# ETH_SWITCH.net
KiCad netlist of a schematic drawn in Altium Designer
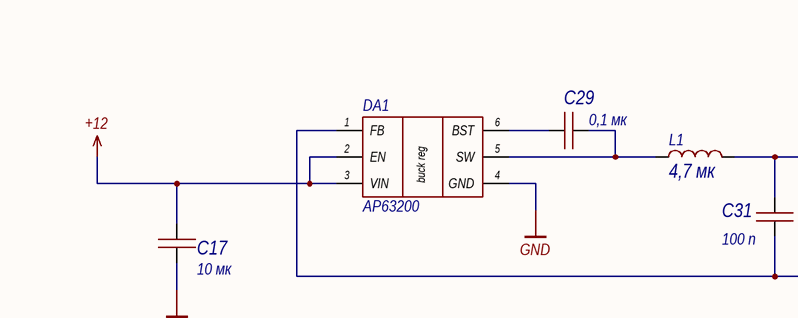
[diagram p0: ETH_SWITCH.SchDoc, top left]
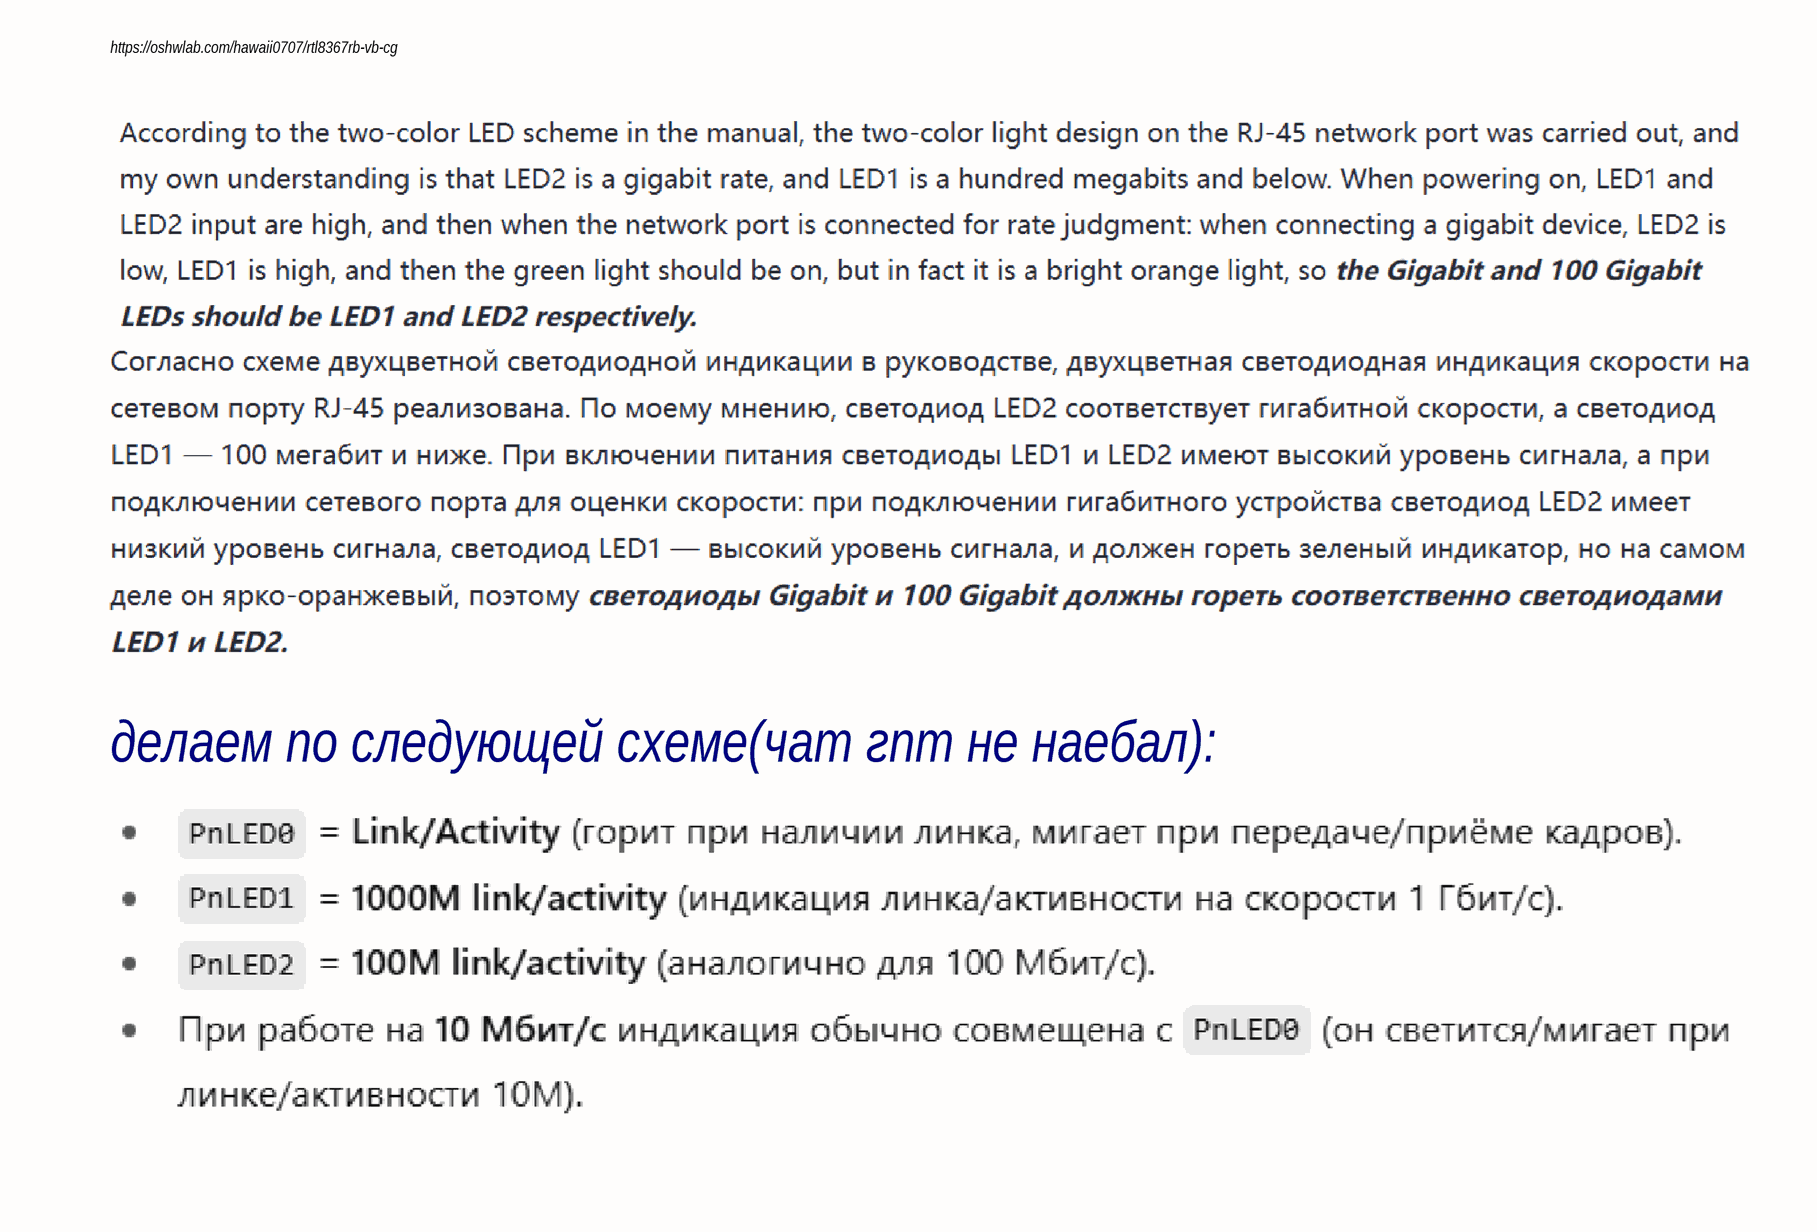
[diagram p1: ETH_SWITCH.SchDoc, top right]
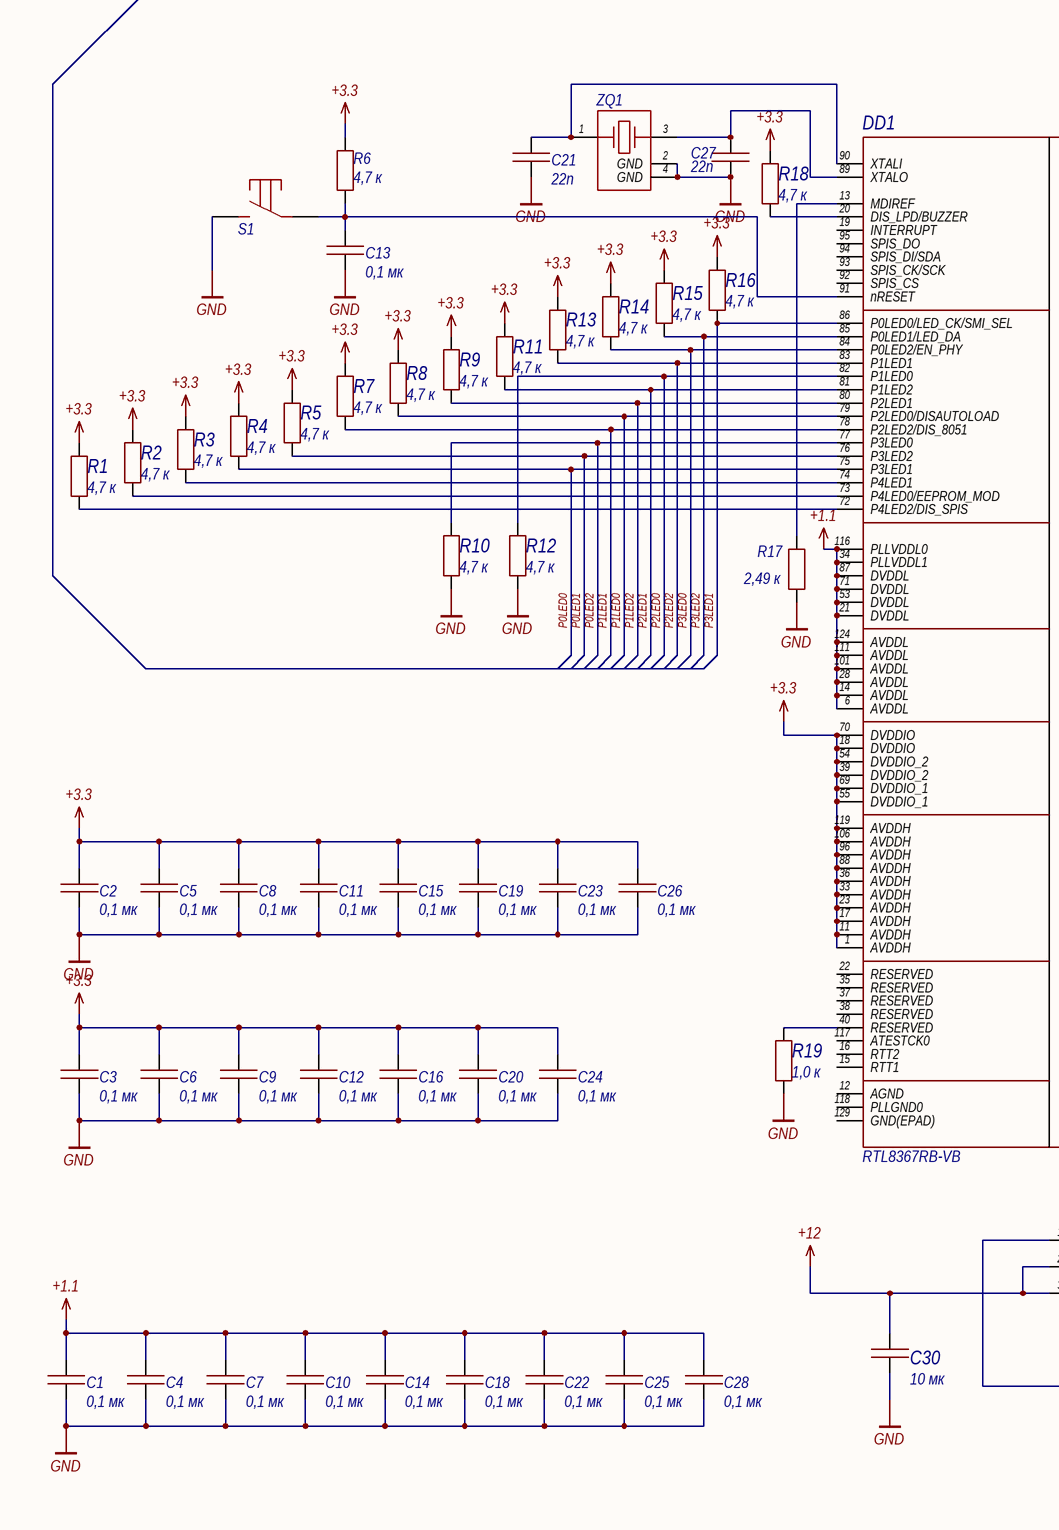
[diagram p2: ETH_SWITCH.SchDoc, bottom left]
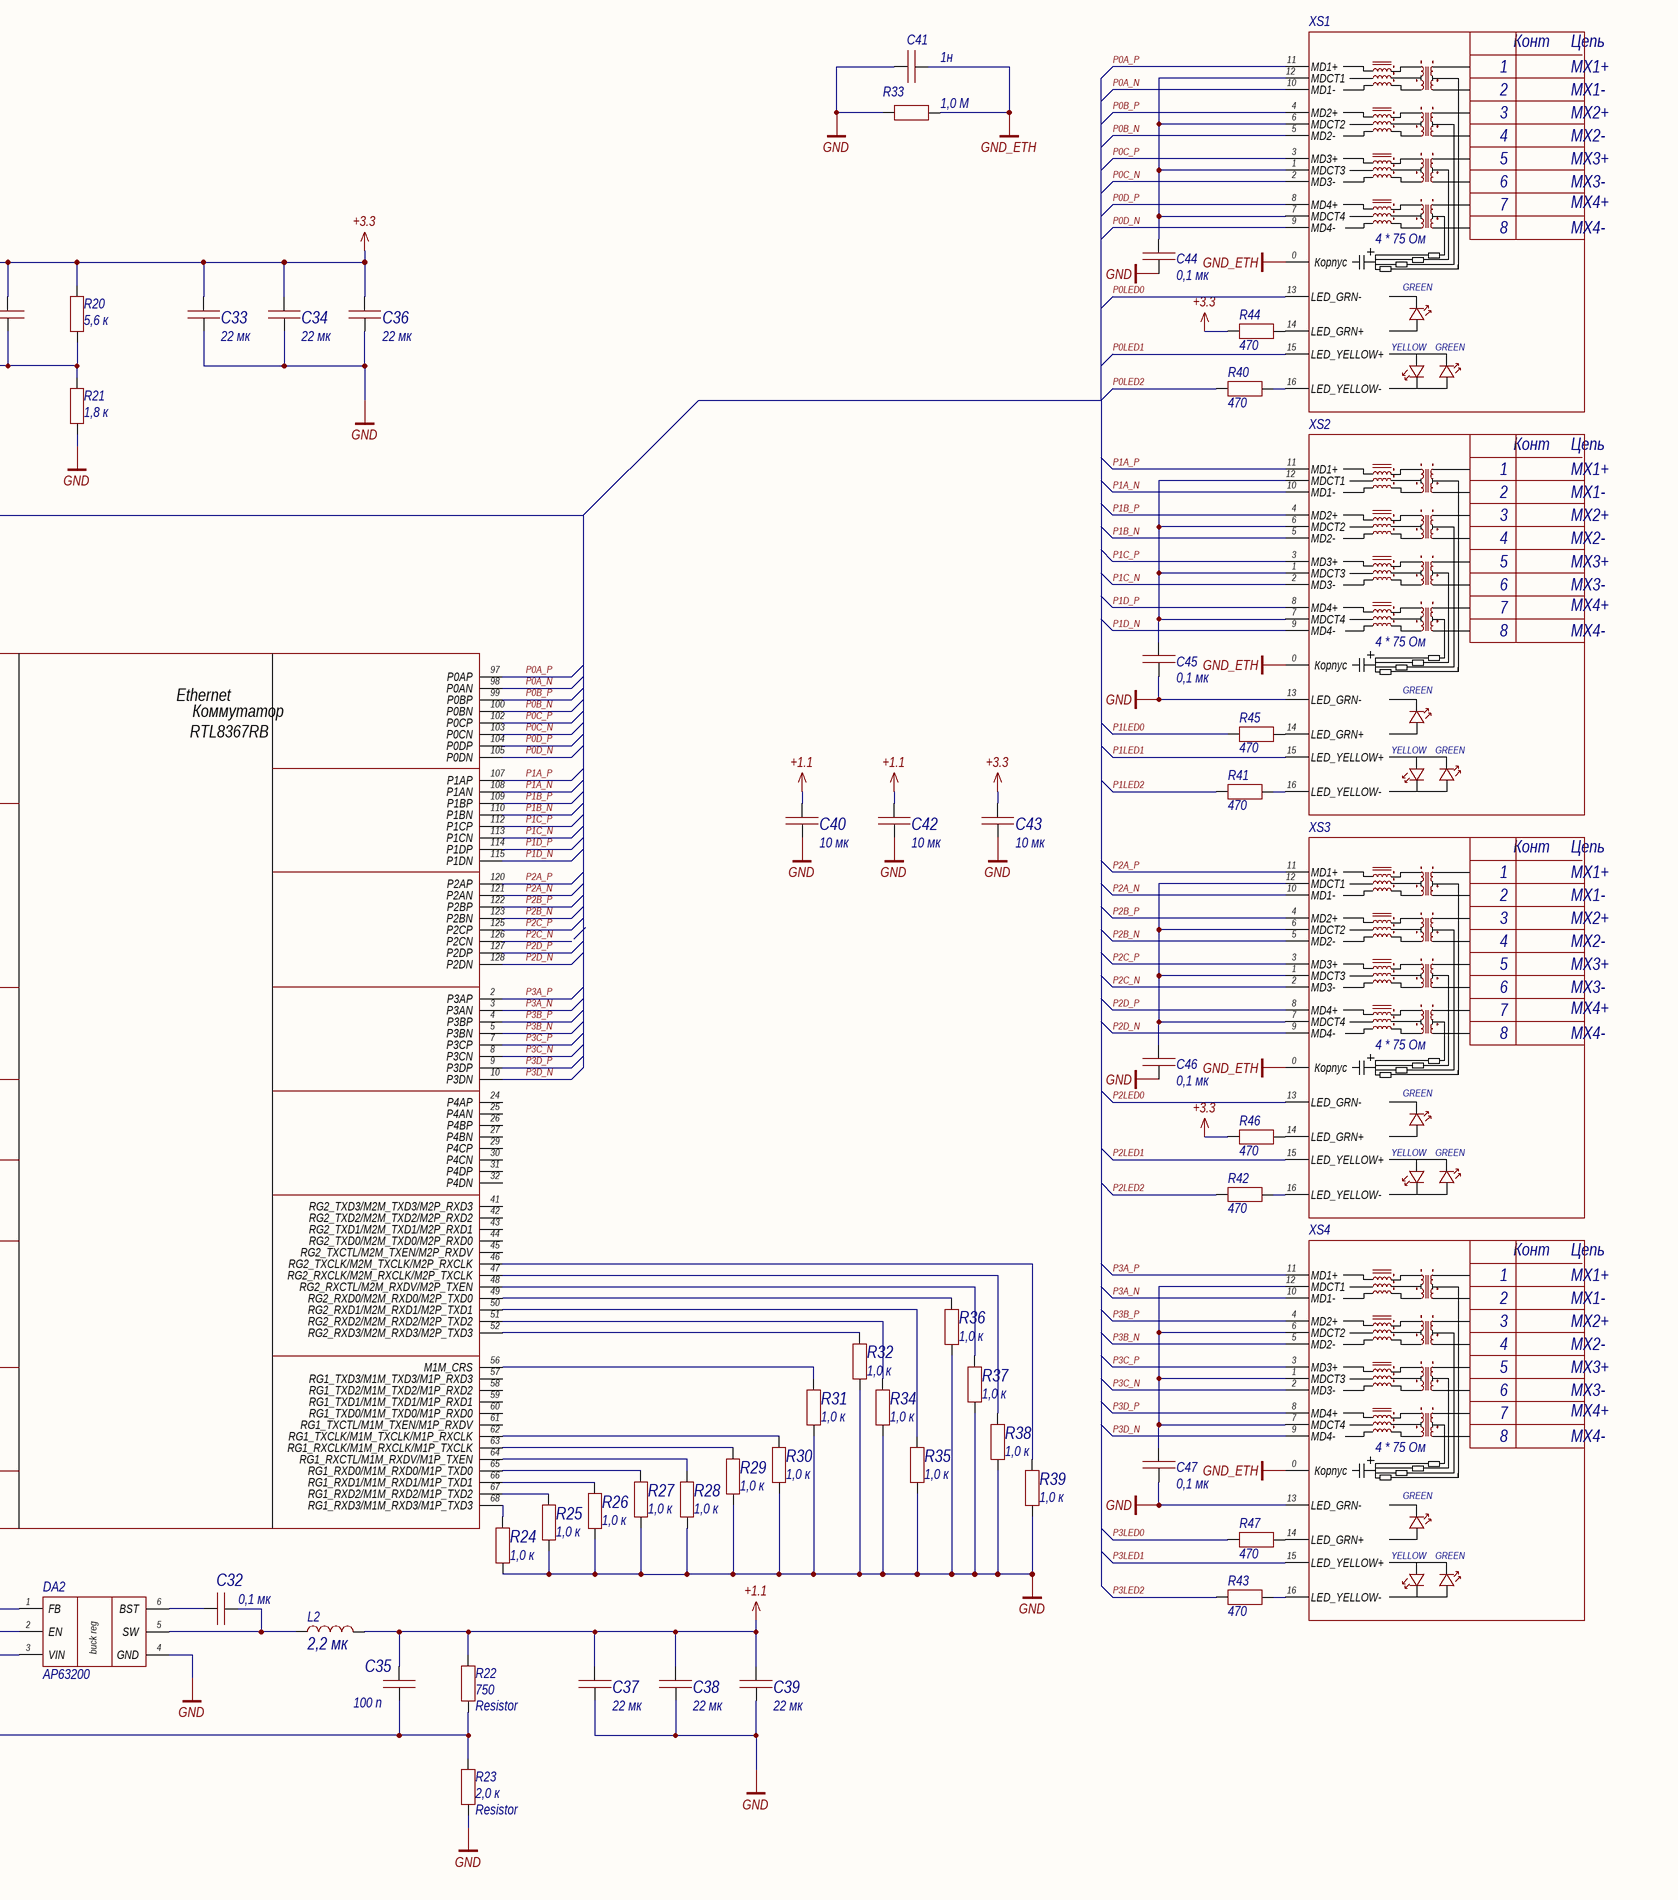
[diagram p3: ETH_SWITCH.SchDoc, bottom right]

(export (version "E")
  (design (tool "Eeschema 10.0.6"))
  (components
    (comp (ref "C1")
      (value "0,1 мк")
      (footprint "0402C")
      (description "Конденсатор 0402C ёмкостью 0,1 мк 10%, 16 В, X7R")
      (fields
        (field (name "PART NUMBER") "Capacitor_0,1u_10_16V_X7R_0603C")
        (field (name "TOLERANCE") "10%")
        (field (name "АВТОР") "rreali")
      )
      (libsource (lib "Hydrolib") (part "Capacitor"))
    )
    (comp (ref "C2")
      (value "0,1 мк")
      (footprint "0402C")
      (description "Конденсатор 0402C ёмкостью 0,1 мк 10%, 16 В, X7R")
      (fields
        (field (name "PART NUMBER") "Capacitor_0,1u_10_16V_X7R_0603C")
        (field (name "TOLERANCE") "10%")
        (field (name "АВТОР") "rreali")
      )
      (libsource (lib "Hydrolib") (part "Capacitor"))
    )
    (comp (ref "C3")
      (value "0,1 мк")
      (footprint "0402C")
      (description "Конденсатор 0402C ёмкостью 0,1 мк 10%, 16 В, X7R")
      (fields
        (field (name "PART NUMBER") "Capacitor_0,1u_10_16V_X7R_0603C")
        (field (name "TOLERANCE") "10%")
        (field (name "АВТОР") "rreali")
      )
      (libsource (lib "Hydrolib") (part "Capacitor"))
    )
    (comp (ref "C4")
      (value "0,1 мк")
      (footprint "0402C")
      (description "Конденсатор 0402C ёмкостью 0,1 мк 10%, 16 В, X7R")
      (fields
        (field (name "PART NUMBER") "Capacitor_0,1u_10_16V_X7R_0603C")
        (field (name "TOLERANCE") "10%")
        (field (name "АВТОР") "rreali")
      )
      (libsource (lib "Hydrolib") (part "Capacitor"))
    )
    (comp (ref "C5")
      (value "0,1 мк")
      (footprint "0402C")
      (description "Конденсатор 0402C ёмкостью 0,1 мк 10%, 16 В, X7R")
      (fields
        (field (name "PART NUMBER") "Capacitor_0,1u_10_16V_X7R_0603C")
        (field (name "TOLERANCE") "10%")
        (field (name "АВТОР") "rreali")
      )
      (libsource (lib "Hydrolib") (part "Capacitor"))
    )
    (comp (ref "C6")
      (value "0,1 мк")
      (footprint "0402C")
      (description "Конденсатор 0402C ёмкостью 0,1 мк 10%, 16 В, X7R")
      (fields
        (field (name "PART NUMBER") "Capacitor_0,1u_10_16V_X7R_0603C")
        (field (name "TOLERANCE") "10%")
        (field (name "АВТОР") "rreali")
      )
      (libsource (lib "Hydrolib") (part "Capacitor"))
    )
    (comp (ref "C7")
      (value "0,1 мк")
      (footprint "0402C")
      (description "Конденсатор 0402C ёмкостью 0,1 мк 10%, 16 В, X7R")
      (fields
        (field (name "PART NUMBER") "Capacitor_0,1u_10_16V_X7R_0603C")
        (field (name "TOLERANCE") "10%")
        (field (name "АВТОР") "rreali")
      )
      (libsource (lib "Hydrolib") (part "Capacitor"))
    )
    (comp (ref "C8")
      (value "0,1 мк")
      (footprint "0402C")
      (description "Конденсатор 0402C ёмкостью 0,1 мк 10%, 16 В, X7R")
      (fields
        (field (name "PART NUMBER") "Capacitor_0,1u_10_16V_X7R_0603C")
        (field (name "TOLERANCE") "10%")
        (field (name "АВТОР") "rreali")
      )
      (libsource (lib "Hydrolib") (part "Capacitor"))
    )
    (comp (ref "C9")
      (value "0,1 мк")
      (footprint "0402C")
      (description "Конденсатор 0402C ёмкостью 0,1 мк 10%, 16 В, X7R")
      (fields
        (field (name "PART NUMBER") "Capacitor_0,1u_10_16V_X7R_0603C")
        (field (name "TOLERANCE") "10%")
        (field (name "АВТОР") "rreali")
      )
      (libsource (lib "Hydrolib") (part "Capacitor"))
    )
    (comp (ref "C10")
      (value "0,1 мк")
      (footprint "0402C")
      (description "Конденсатор 0402C ёмкостью 0,1 мк 10%, 16 В, X7R")
      (fields
        (field (name "PART NUMBER") "Capacitor_0,1u_10_16V_X7R_0603C")
        (field (name "TOLERANCE") "10%")
        (field (name "АВТОР") "rreali")
      )
      (libsource (lib "Hydrolib") (part "Capacitor"))
    )
    (comp (ref "C11")
      (value "0,1 мк")
      (footprint "0402C")
      (description "Конденсатор 0402C ёмкостью 0,1 мк 10%, 16 В, X7R")
      (fields
        (field (name "PART NUMBER") "Capacitor_0,1u_10_16V_X7R_0603C")
        (field (name "TOLERANCE") "10%")
        (field (name "АВТОР") "rreali")
      )
      (libsource (lib "Hydrolib") (part "Capacitor"))
    )
    (comp (ref "C12")
      (value "0,1 мк")
      (footprint "0402C")
      (description "Конденсатор 0402C ёмкостью 0,1 мк 10%, 16 В, X7R")
      (fields
        (field (name "PART NUMBER") "Capacitor_0,1u_10_16V_X7R_0603C")
        (field (name "TOLERANCE") "10%")
        (field (name "АВТОР") "rreali")
      )
      (libsource (lib "Hydrolib") (part "Capacitor"))
    )
    (comp (ref "C13")
      (value "0,1 мк")
      (footprint "0603C")
      (description "Конденсатор 0603C ёмкостью 0,1 мк 10%, 50 В, X7R")
      (fields (field (name "PART NUMBER") "Capacitor_0,1u_10_50V_X7R_0603C") (field (name "TOLERANCE") "10%"))
      (libsource (lib "Hydrolib") (part "Capacitor"))
    )
    (comp (ref "C14")
      (value "0,1 мк")
      (footprint "0402C")
      (description "Конденсатор 0402C ёмкостью 0,1 мк 10%, 16 В, X7R")
      (fields
        (field (name "PART NUMBER") "Capacitor_0,1u_10_16V_X7R_0603C")
        (field (name "TOLERANCE") "10%")
        (field (name "АВТОР") "rreali")
      )
      (libsource (lib "Hydrolib") (part "Capacitor"))
    )
    (comp (ref "C15")
      (value "0,1 мк")
      (footprint "0402C")
      (description "Конденсатор 0402C ёмкостью 0,1 мк 10%, 16 В, X7R")
      (fields
        (field (name "PART NUMBER") "Capacitor_0,1u_10_16V_X7R_0603C")
        (field (name "TOLERANCE") "10%")
        (field (name "АВТОР") "rreali")
      )
      (libsource (lib "Hydrolib") (part "Capacitor"))
    )
    (comp (ref "C16")
      (value "0,1 мк")
      (footprint "0402C")
      (description "Конденсатор 0402C ёмкостью 0,1 мк 10%, 16 В, X7R")
      (fields
        (field (name "PART NUMBER") "Capacitor_0,1u_10_16V_X7R_0603C")
        (field (name "TOLERANCE") "10%")
        (field (name "АВТОР") "rreali")
      )
      (libsource (lib "Hydrolib") (part "Capacitor"))
    )
    (comp (ref "C17")
      (value "10 мк")
      (footprint "1210C")
      (description "Конденсатор 1210C ёмкостью 10 мк 10%, 35 В, X7R")
      (fields (field (name "PART NUMBER") "Capacitor_10u_10_35V_X7R_1210C") (field (name "TOLERANCE") "10%"))
      (libsource (lib "Hydrolib") (part "Capacitor"))
    )
    (comp (ref "C18")
      (value "0,1 мк")
      (footprint "0402C")
      (description "Конденсатор 0402C ёмкостью 0,1 мк 10%, 16 В, X7R")
      (fields
        (field (name "PART NUMBER") "Capacitor_0,1u_10_16V_X7R_0603C")
        (field (name "TOLERANCE") "10%")
        (field (name "АВТОР") "rreali")
      )
      (libsource (lib "Hydrolib") (part "Capacitor"))
    )
    (comp (ref "C19")
      (value "0,1 мк")
      (footprint "0402C")
      (description "Конденсатор 0402C ёмкостью 0,1 мк 10%, 16 В, X7R")
      (fields
        (field (name "PART NUMBER") "Capacitor_0,1u_10_16V_X7R_0603C")
        (field (name "TOLERANCE") "10%")
        (field (name "АВТОР") "rreali")
      )
      (libsource (lib "Hydrolib") (part "Capacitor"))
    )
    (comp (ref "C20")
      (value "0,1 мк")
      (footprint "0402C")
      (description "Конденсатор 0402C ёмкостью 0,1 мк 10%, 16 В, X7R")
      (fields
        (field (name "PART NUMBER") "Capacitor_0,1u_10_16V_X7R_0603C")
        (field (name "TOLERANCE") "10%")
        (field (name "АВТОР") "rreali")
      )
      (libsource (lib "Hydrolib") (part "Capacitor"))
    )
    (comp (ref "C21")
      (value "22п")
      (footprint "0603C")
      (description "Конденсатор 0603C ёмкостью 22п 5%, 50 В, NP0")
      (fields
        (field (name "PART NUMBER") "GRM1885C1H220J")
        (field (name "TOLERANCE") "5%")
        (field (name "АВТОР") "rreali")
      )
      (libsource (lib "Hydrolib") (part "Capacitor"))
    )
    (comp (ref "C22")
      (value "0,1 мк")
      (footprint "0402C")
      (description "Конденсатор 0402C ёмкостью 0,1 мк 10%, 16 В, X7R")
      (fields
        (field (name "PART NUMBER") "Capacitor_0,1u_10_16V_X7R_0603C")
        (field (name "TOLERANCE") "10%")
        (field (name "АВТОР") "rreali")
      )
      (libsource (lib "Hydrolib") (part "Capacitor"))
    )
    (comp (ref "C23")
      (value "0,1 мк")
      (footprint "0402C")
      (description "Конденсатор 0402C ёмкостью 0,1 мк 10%, 16 В, X7R")
      (fields
        (field (name "PART NUMBER") "Capacitor_0,1u_10_16V_X7R_0603C")
        (field (name "TOLERANCE") "10%")
        (field (name "АВТОР") "rreali")
      )
      (libsource (lib "Hydrolib") (part "Capacitor"))
    )
    (comp (ref "C24")
      (value "0,1 мк")
      (footprint "0402C")
      (description "Конденсатор 0402C ёмкостью 0,1 мк 10%, 16 В, X7R")
      (fields
        (field (name "PART NUMBER") "Capacitor_0,1u_10_16V_X7R_0603C")
        (field (name "TOLERANCE") "10%")
        (field (name "АВТОР") "rreali")
      )
      (libsource (lib "Hydrolib") (part "Capacitor"))
    )
    (comp (ref "C25")
      (value "0,1 мк")
      (footprint "0402C")
      (description "Конденсатор 0402C ёмкостью 0,1 мк 10%, 16 В, X7R")
      (fields
        (field (name "PART NUMBER") "Capacitor_0,1u_10_16V_X7R_0603C")
        (field (name "TOLERANCE") "10%")
        (field (name "АВТОР") "rreali")
      )
      (libsource (lib "Hydrolib") (part "Capacitor"))
    )
    (comp (ref "C26")
      (value "0,1 мк")
      (footprint "0402C")
      (description "Конденсатор 0402C ёмкостью 0,1 мк 10%, 16 В, X7R")
      (fields
        (field (name "PART NUMBER") "Capacitor_0,1u_10_16V_X7R_0603C")
        (field (name "TOLERANCE") "10%")
        (field (name "АВТОР") "rreali")
      )
      (libsource (lib "Hydrolib") (part "Capacitor"))
    )
    (comp (ref "C27")
      (value "22п")
      (footprint "0603C")
      (description "Конденсатор 0603C ёмкостью 22п 5%, 50 В, NP0")
      (fields
        (field (name "PART NUMBER") "GRM1885C1H220J")
        (field (name "TOLERANCE") "5%")
        (field (name "АВТОР") "rreali")
      )
      (libsource (lib "Hydrolib") (part "Capacitor"))
    )
    (comp (ref "C28")
      (value "0,1 мк")
      (footprint "0402C")
      (description "Конденсатор 0402C ёмкостью 0,1 мк 10%, 16 В, X7R")
      (fields
        (field (name "PART NUMBER") "Capacitor_0,1u_10_16V_X7R_0603C")
        (field (name "TOLERANCE") "10%")
        (field (name "АВТОР") "rreali")
      )
      (libsource (lib "Hydrolib") (part "Capacitor"))
    )
    (comp (ref "C29")
      (value "0,1 мк")
      (footprint "0603C")
      (description "Конденсатор 0603C ёмкостью 0,1 мк 10%, 50 В, X7R")
      (fields (field (name "PART NUMBER") "Capacitor_0,1u_10_50V_X7R_0603C") (field (name "TOLERANCE") "10%"))
      (libsource (lib "Hydrolib") (part "Capacitor"))
    )
    (comp (ref "C30")
      (value "10 мк")
      (footprint "1210C")
      (description "Конденсатор 1210C ёмкостью 10 мк 10%, 35 В, X7R")
      (fields (field (name "PART NUMBER") "Capacitor_10u_10_35V_X7R_1210C") (field (name "TOLERANCE") "10%"))
      (libsource (lib "Hydrolib") (part "Capacitor"))
    )
    (comp (ref "C31")
      (value "100 п")
      (footprint "0603C")
      (description "Конденсатор 0603C ёмкостью 100 п 10%, 50 В, X7R")
      (fields (field (name "PART NUMBER") "Capacitor_100p_10_50V_X7R_0603C") (field (name "TOLERANCE") "10%"))
      (libsource (lib "Hydrolib") (part "Capacitor"))
    )
    (comp (ref "C32")
      (value "0,1 мк")
      (footprint "0603C")
      (description "Конденсатор 0603C ёмкостью 0,1 мк 10%, 50 В, X7R")
      (fields (field (name "PART NUMBER") "Capacitor_0,1u_10_50V_X7R_0603C") (field (name "TOLERANCE") "10%"))
      (libsource (lib "Hydrolib") (part "Capacitor"))
    )
    (comp (ref "C33")
      (value "22 мк")
      (footprint "1210C")
      (description "Конденсатор 1210C ёмкостью 22 мк 10%, 25 В, X7R")
      (fields (field (name "PART NUMBER") "Capacitor_22u_10_25V_X7R_1210C") (field (name "TOLERANCE") "10%"))
      (libsource (lib "Hydrolib") (part "Capacitor"))
    )
    (comp (ref "C34")
      (value "22 мк")
      (footprint "1210C")
      (description "Конденсатор 1210C ёмкостью 22 мк 10%, 25 В, X7R")
      (fields (field (name "PART NUMBER") "Capacitor_22u_10_25V_X7R_1210C") (field (name "TOLERANCE") "10%"))
      (libsource (lib "Hydrolib") (part "Capacitor"))
    )
    (comp (ref "C35")
      (value "100 п")
      (footprint "0603C")
      (description "Конденсатор 0603C ёмкостью 100 п 10%, 50 В, X7R")
      (fields (field (name "PART NUMBER") "Capacitor_100p_10_50V_X7R_0603C") (field (name "TOLERANCE") "10%"))
      (libsource (lib "Hydrolib") (part "Capacitor"))
    )
    (comp (ref "C36")
      (value "22 мк")
      (footprint "1210C")
      (description "Конденсатор 1210C ёмкостью 22 мк 10%, 25 В, X7R")
      (fields (field (name "PART NUMBER") "Capacitor_22u_10_25V_X7R_1210C") (field (name "TOLERANCE") "10%"))
      (libsource (lib "Hydrolib") (part "Capacitor"))
    )
    (comp (ref "C37")
      (value "22 мк")
      (footprint "1210C")
      (description "Конденсатор 1210C ёмкостью 22 мк 10%, 25 В, X7R")
      (fields (field (name "PART NUMBER") "Capacitor_22u_10_25V_X7R_1210C") (field (name "TOLERANCE") "10%"))
      (libsource (lib "Hydrolib") (part "Capacitor"))
    )
    (comp (ref "C38")
      (value "22 мк")
      (footprint "1210C")
      (description "Конденсатор 1210C ёмкостью 22 мк 10%, 25 В, X7R")
      (fields (field (name "PART NUMBER") "Capacitor_22u_10_25V_X7R_1210C") (field (name "TOLERANCE") "10%"))
      (libsource (lib "Hydrolib") (part "Capacitor"))
    )
    (comp (ref "C39")
      (value "22 мк")
      (footprint "1210C")
      (description "Конденсатор 1210C ёмкостью 22 мк 10%, 25 В, X7R")
      (fields (field (name "PART NUMBER") "Capacitor_22u_10_25V_X7R_1210C") (field (name "TOLERANCE") "10%"))
      (libsource (lib "Hydrolib") (part "Capacitor"))
    )
    (comp (ref "C40")
      (value "10 мк")
      (footprint "1210C")
      (description "Конденсатор 1210C ёмкостью 10 мк 10%, 35 В, X7R")
      (fields (field (name "PART NUMBER") "Capacitor_10u_10_35V_X7R_1210C") (field (name "TOLERANCE") "10%"))
      (libsource (lib "Hydrolib") (part "Capacitor"))
    )
    (comp (ref "C41")
      (value "1н")
      (footprint "1210C")
      (description "Конденсатор 1210C ёмкостью 1н 10%, 1000 В, X7R")
      (fields
        (field (name "PART NUMBER") "Capacitor_1n_10_1000V_X7R_1206C")
        (field (name "TOLERANCE") "10%")
        (field (name "АВТОР") "rreali")
      )
      (libsource (lib "Hydrolib") (part "Capacitor"))
    )
    (comp (ref "C42")
      (value "10 мк")
      (footprint "1210C")
      (description "Конденсатор 1210C ёмкостью 10 мк 10%, 35 В, X7R")
      (fields (field (name "PART NUMBER") "Capacitor_10u_10_35V_X7R_1210C") (field (name "TOLERANCE") "10%"))
      (libsource (lib "Hydrolib") (part "Capacitor"))
    )
    (comp (ref "C43")
      (value "10 мк")
      (footprint "1210C")
      (description "Конденсатор 1210C ёмкостью 10 мк 10%, 35 В, X7R")
      (fields (field (name "PART NUMBER") "Capacitor_10u_10_35V_X7R_1210C") (field (name "TOLERANCE") "10%"))
      (libsource (lib "Hydrolib") (part "Capacitor"))
    )
    (comp (ref "C44")
      (value "0,1 мк")
      (footprint "0603C")
      (description "Конденсатор 0603C ёмкостью 0,1 мк 10%, 50 В, X7R")
      (fields (field (name "PART NUMBER") "Capacitor_0,1u_10_50V_X7R_0603C") (field (name "TOLERANCE") "10%"))
      (libsource (lib "Hydrolib") (part "Capacitor"))
    )
    (comp (ref "C45")
      (value "0,1 мк")
      (footprint "0603C")
      (description "Конденсатор 0603C ёмкостью 0,1 мк 10%, 50 В, X7R")
      (fields (field (name "PART NUMBER") "Capacitor_0,1u_10_50V_X7R_0603C") (field (name "TOLERANCE") "10%"))
      (libsource (lib "Hydrolib") (part "Capacitor"))
    )
    (comp (ref "C46")
      (value "0,1 мк")
      (footprint "0603C")
      (description "Конденсатор 0603C ёмкостью 0,1 мк 10%, 50 В, X7R")
      (fields (field (name "PART NUMBER") "Capacitor_0,1u_10_50V_X7R_0603C") (field (name "TOLERANCE") "10%"))
      (libsource (lib "Hydrolib") (part "Capacitor"))
    )
    (comp (ref "C47")
      (value "0,1 мк")
      (footprint "0603C")
      (description "Конденсатор 0603C ёмкостью 0,1 мк 10%, 50 В, X7R")
      (fields (field (name "PART NUMBER") "Capacitor_0,1u_10_50V_X7R_0603C") (field (name "TOLERANCE") "10%"))
      (libsource (lib "Hydrolib") (part "Capacitor"))
    )
    (comp (ref "DA1")
      (value "AP63200")
      (footprint "TSOT26")
      (description "DC-DC понижающий преобразователь, Vin: 3.8 - 40 В, adj, 2 А")
      (libsource (lib "Hydrolib") (part "AP63200"))
    )
    (comp (ref "DA2")
      (value "AP63200")
      (footprint "TSOT26")
      (description "DC-DC понижающий преобразователь, Vin: 3.8 - 40 В, adj, 2 А")
      (libsource (lib "Hydrolib") (part "AP63200"))
    )
    (comp (ref "DD1")
      (value "RTL8367RB-VB")
      (footprint "LQFP128_14x14_exposed_pad")
      (description "Управляемый коммутатор второго уровня на 5+2 порта 10/100/1000M")
      (fields (field (name "АВТОР") "rreali"))
      (libsource (lib "Hydrolib") (part "RTL8367RB-VB_gost"))
    )
    (comp (ref "L1")
      (value "4,7 мк")
      (footprint "B82462G4")
      (description "Индуктивность на 4,7 мкГн, номинальный ток 2,5 А")
      (fields (field (name "PART NUMBER") "B82472G6472M") (field (name "АВТОР") "rreali"))
      (libsource (lib "Hydrolib") (part "Inductance"))
    )
    (comp (ref "L2")
      (value "2,2 мк")
      (footprint "CDRH6D12")
      (description "Индуктивность на 2,2 мкГн, номинальный ток 2,5 А")
      (fields (field (name "PART NUMBER") "CDRH6D12NP-2R2NC") (field (name "АВТОР") "rreali"))
      (libsource (lib "Hydrolib") (part "Inductance_1-3"))
    )
    (comp (ref "R1")
      (value "4,7 к")
      (footprint "0402R")
      (description "Резистор номиналом 4,7 кОм 1%")
      (fields
        (field (name "PART NUMBER") "Resistor_4.7k_1_0402")
        (field (name "TOLERANCE") "1%")
        (field (name "АВТОР") "rreali")
      )
      (libsource (lib "") (part "Resistor_1"))
    )
    (comp (ref "R2")
      (value "4,7 к")
      (footprint "0402R")
      (description "Резистор номиналом 4,7 кОм 1%")
      (fields
        (field (name "PART NUMBER") "Resistor_4.7k_1_0402")
        (field (name "TOLERANCE") "1%")
        (field (name "АВТОР") "rreali")
      )
      (libsource (lib "") (part "Resistor_1"))
    )
    (comp (ref "R3")
      (value "4,7 к")
      (footprint "0402R")
      (description "Резистор номиналом 4,7 кОм 1%")
      (fields
        (field (name "PART NUMBER") "Resistor_4.7k_1_0402")
        (field (name "TOLERANCE") "1%")
        (field (name "АВТОР") "rreali")
      )
      (libsource (lib "") (part "Resistor_1"))
    )
    (comp (ref "R4")
      (value "4,7 к")
      (footprint "0402R")
      (description "Резистор номиналом 4,7 кОм 1%")
      (fields
        (field (name "PART NUMBER") "Resistor_4.7k_1_0402")
        (field (name "TOLERANCE") "1%")
        (field (name "АВТОР") "rreali")
      )
      (libsource (lib "") (part "Resistor_1"))
    )
    (comp (ref "R5")
      (value "4,7 к")
      (footprint "0402R")
      (description "Резистор номиналом 4,7 кОм 1%")
      (fields
        (field (name "PART NUMBER") "Resistor_4.7k_1_0402")
        (field (name "TOLERANCE") "1%")
        (field (name "АВТОР") "rreali")
      )
      (libsource (lib "") (part "Resistor_1"))
    )
    (comp (ref "R6")
      (value "4,7 к")
      (footprint "0402R")
      (description "Резистор номиналом 4,7 кОм 1%")
      (fields
        (field (name "PART NUMBER") "Resistor_4.7k_1_0402")
        (field (name "TOLERANCE") "1%")
        (field (name "АВТОР") "rreali")
      )
      (libsource (lib "Hydrolib") (part "Resistor"))
    )
    (comp (ref "R7")
      (value "4,7 к")
      (footprint "0402R")
      (description "Резистор номиналом 4,7 кОм 1%")
      (fields
        (field (name "PART NUMBER") "Resistor_4.7k_1_0402")
        (field (name "TOLERANCE") "1%")
        (field (name "АВТОР") "rreali")
      )
      (libsource (lib "") (part "Resistor_1"))
    )
    (comp (ref "R8")
      (value "4,7 к")
      (footprint "0402R")
      (description "Резистор номиналом 4,7 кОм 1%")
      (fields
        (field (name "PART NUMBER") "Resistor_4.7k_1_0402")
        (field (name "TOLERANCE") "1%")
        (field (name "АВТОР") "rreali")
      )
      (libsource (lib "") (part "Resistor_1"))
    )
    (comp (ref "R9")
      (value "4,7 к")
      (footprint "0402R")
      (description "Резистор номиналом 4,7 кОм 1%")
      (fields
        (field (name "PART NUMBER") "Resistor_4.7k_1_0402")
        (field (name "TOLERANCE") "1%")
        (field (name "АВТОР") "rreali")
      )
      (libsource (lib "") (part "Resistor_1"))
    )
    (comp (ref "R10")
      (value "4,7 к")
      (footprint "0402R")
      (description "Резистор номиналом 4,7 кОм 1%")
      (fields
        (field (name "PART NUMBER") "Resistor_4.7k_1_0402")
        (field (name "TOLERANCE") "1%")
        (field (name "АВТОР") "rreali")
      )
      (libsource (lib "") (part "Resistor_1"))
    )
    (comp (ref "R11")
      (value "4,7 к")
      (footprint "0402R")
      (description "Резистор номиналом 4,7 кОм 1%")
      (fields
        (field (name "PART NUMBER") "Resistor_4.7k_1_0402")
        (field (name "TOLERANCE") "1%")
        (field (name "АВТОР") "rreali")
      )
      (libsource (lib "") (part "Resistor_1"))
    )
    (comp (ref "R12")
      (value "4,7 к")
      (footprint "0402R")
      (description "Резистор номиналом 4,7 кОм 1%")
      (fields
        (field (name "PART NUMBER") "Resistor_4.7k_1_0402")
        (field (name "TOLERANCE") "1%")
        (field (name "АВТОР") "rreali")
      )
      (libsource (lib "") (part "Resistor_1"))
    )
    (comp (ref "R13")
      (value "4,7 к")
      (footprint "0402R")
      (description "Резистор номиналом 4,7 кОм 1%")
      (fields
        (field (name "PART NUMBER") "Resistor_4.7k_1_0402")
        (field (name "TOLERANCE") "1%")
        (field (name "АВТОР") "rreali")
      )
      (libsource (lib "") (part "Resistor_1"))
    )
    (comp (ref "R14")
      (value "4,7 к")
      (footprint "0402R")
      (description "Резистор номиналом 4,7 кОм 1%")
      (fields
        (field (name "PART NUMBER") "Resistor_4.7k_1_0402")
        (field (name "TOLERANCE") "1%")
        (field (name "АВТОР") "rreali")
      )
      (libsource (lib "") (part "Resistor_1"))
    )
    (comp (ref "R15")
      (value "4,7 к")
      (footprint "0402R")
      (description "Резистор номиналом 4,7 кОм 1%")
      (fields
        (field (name "PART NUMBER") "Resistor_4.7k_1_0402")
        (field (name "TOLERANCE") "1%")
        (field (name "АВТОР") "rreali")
      )
      (libsource (lib "") (part "Resistor_1"))
    )
    (comp (ref "R16")
      (value "4,7 к")
      (footprint "0402R")
      (description "Резистор номиналом 4,7 кОм 1%")
      (fields
        (field (name "PART NUMBER") "Resistor_4.7k_1_0402")
        (field (name "TOLERANCE") "1%")
        (field (name "АВТОР") "rreali")
      )
      (libsource (lib "") (part "Resistor_1"))
    )
    (comp (ref "R17")
      (value "2,49 к")
      (footprint "0603R")
      (description "0.1Вт 0603 2.49 кОм, 1%, Чип резистор")
      (fields
        (field (name "PART NUMBER") "RC0603FR-072K49L")
        (field (name "TOLERANCE") "1%")
        (field (name "АВТОР") "rreali")
      )
      (libsource (lib "") (part "Resistor_1"))
    )
    (comp (ref "R18")
      (value "4,7 к")
      (footprint "0402R")
      (description "Резистор номиналом 4,7 кОм 1%")
      (fields
        (field (name "PART NUMBER") "Resistor_4.7k_1_0402")
        (field (name "TOLERANCE") "1%")
        (field (name "АВТОР") "rreali")
      )
      (libsource (lib "") (part "Resistor_1"))
    )
    (comp (ref "R19")
      (value "1,0 к")
      (footprint "0402R")
      (description "Резистор номиналом 1,0 кОм 1%")
      (fields
        (field (name "PART NUMBER") "Resistor_1.0k_1_0402")
        (field (name "TOLERANCE") "1%")
        (field (name "АВТОР") "rreali")
      )
      (libsource (lib "Hydrolib") (part "Resistor"))
    )
    (comp (ref "R20")
      (value "5,6 к")
      (footprint "0603R")
      (description "Резистор номиналом 5,6 кОм 1%")
      (fields (field (name "PART NUMBER") "Resistor_5.6k_1_0603") (field (name "TOLERANCE") "1%"))
      (libsource (lib "") (part "Resistor_1"))
    )
    (comp (ref "R21")
      (value "1,8 к")
      (footprint "0603R")
      (description "Резистор номиналом 1,8 кОм 1%")
      (fields (field (name "PART NUMBER") "Resistor_1.8k_1_0603") (field (name "TOLERANCE") "1%"))
      (libsource (lib "") (part "Resistor_1"))
    )
    (comp (ref "R22")
      (value "Resistor")
      (footprint "0603R")
      (description "Резистор номиналом 750 Ом 1%")
      (fields
        (field (name "ALTIUM_VALUE") "750")
        (field (name "PART NUMBER") "Resistor_750_1_0603")
        (field (name "TOLERANCE") "1%")
      )
      (libsource (lib "") (part "Resistor_1"))
    )
    (comp (ref "R23")
      (value "Resistor")
      (footprint "0603R")
      (description "Резистор номиналом 2,0 кОм 1%")
      (fields
        (field (name "ALTIUM_VALUE") "2,0 к")
        (field (name "PART NUMBER") "Resistor_2.0k_1_0603")
        (field (name "TOLERANCE") "1%")
      )
      (libsource (lib "") (part "Resistor_1"))
    )
    (comp (ref "R24")
      (value "1,0 к")
      (footprint "0402R")
      (description "Резистор номиналом 1,0 кОм 1%")
      (fields
        (field (name "PART NUMBER") "Resistor_1.0k_1_0402")
        (field (name "TOLERANCE") "1%")
        (field (name "АВТОР") "rreali")
      )
      (libsource (lib "Hydrolib") (part "Resistor"))
    )
    (comp (ref "R25")
      (value "1,0 к")
      (footprint "0402R")
      (description "Резистор номиналом 1,0 кОм 1%")
      (fields
        (field (name "PART NUMBER") "Resistor_1.0k_1_0402")
        (field (name "TOLERANCE") "1%")
        (field (name "АВТОР") "rreali")
      )
      (libsource (lib "Hydrolib") (part "Resistor"))
    )
    (comp (ref "R26")
      (value "1,0 к")
      (footprint "0402R")
      (description "Резистор номиналом 1,0 кОм 1%")
      (fields
        (field (name "PART NUMBER") "Resistor_1.0k_1_0402")
        (field (name "TOLERANCE") "1%")
        (field (name "АВТОР") "rreali")
      )
      (libsource (lib "Hydrolib") (part "Resistor"))
    )
    (comp (ref "R27")
      (value "1,0 к")
      (footprint "0402R")
      (description "Резистор номиналом 1,0 кОм 1%")
      (fields
        (field (name "PART NUMBER") "Resistor_1.0k_1_0402")
        (field (name "TOLERANCE") "1%")
        (field (name "АВТОР") "rreali")
      )
      (libsource (lib "Hydrolib") (part "Resistor"))
    )
    (comp (ref "R28")
      (value "1,0 к")
      (footprint "0402R")
      (description "Резистор номиналом 1,0 кОм 1%")
      (fields
        (field (name "PART NUMBER") "Resistor_1.0k_1_0402")
        (field (name "TOLERANCE") "1%")
        (field (name "АВТОР") "rreali")
      )
      (libsource (lib "Hydrolib") (part "Resistor"))
    )
    (comp (ref "R29")
      (value "1,0 к")
      (footprint "0402R")
      (description "Резистор номиналом 1,0 кОм 1%")
      (fields
        (field (name "PART NUMBER") "Resistor_1.0k_1_0402")
        (field (name "TOLERANCE") "1%")
        (field (name "АВТОР") "rreali")
      )
      (libsource (lib "Hydrolib") (part "Resistor"))
    )
    (comp (ref "R30")
      (value "1,0 к")
      (footprint "0402R")
      (description "Резистор номиналом 1,0 кОм 1%")
      (fields
        (field (name "PART NUMBER") "Resistor_1.0k_1_0402")
        (field (name "TOLERANCE") "1%")
        (field (name "АВТОР") "rreali")
      )
      (libsource (lib "Hydrolib") (part "Resistor"))
    )
    (comp (ref "R31")
      (value "1,0 к")
      (footprint "0402R")
      (description "Резистор номиналом 1,0 кОм 1%")
      (fields
        (field (name "PART NUMBER") "Resistor_1.0k_1_0402")
        (field (name "TOLERANCE") "1%")
        (field (name "АВТОР") "rreali")
      )
      (libsource (lib "Hydrolib") (part "Resistor"))
    )
    (comp (ref "R32")
      (value "1,0 к")
      (footprint "0402R")
      (description "Резистор номиналом 1,0 кОм 1%")
      (fields
        (field (name "PART NUMBER") "Resistor_1.0k_1_0402")
        (field (name "TOLERANCE") "1%")
        (field (name "АВТОР") "rreali")
      )
      (libsource (lib "Hydrolib") (part "Resistor"))
    )
    (comp (ref "R33")
      (value "1,0 М")
      (footprint "0603R")
      (description "Резистор номиналом 1,0 МОм 1%")
      (fields (field (name "PART NUMBER") "Resistor_1.0M_1_0603") (field (name "TOLERANCE") "1%"))
      (libsource (lib "Hydrolib") (part "Resistor"))
    )
    (comp (ref "R34")
      (value "1,0 к")
      (footprint "0402R")
      (description "Резистор номиналом 1,0 кОм 1%")
      (fields
        (field (name "PART NUMBER") "Resistor_1.0k_1_0402")
        (field (name "TOLERANCE") "1%")
        (field (name "АВТОР") "rreali")
      )
      (libsource (lib "Hydrolib") (part "Resistor"))
    )
    (comp (ref "R35")
      (value "1,0 к")
      (footprint "0402R")
      (description "Резистор номиналом 1,0 кОм 1%")
      (fields
        (field (name "PART NUMBER") "Resistor_1.0k_1_0402")
        (field (name "TOLERANCE") "1%")
        (field (name "АВТОР") "rreali")
      )
      (libsource (lib "Hydrolib") (part "Resistor"))
    )
    (comp (ref "R36")
      (value "1,0 к")
      (footprint "0402R")
      (description "Резистор номиналом 1,0 кОм 1%")
      (fields
        (field (name "PART NUMBER") "Resistor_1.0k_1_0402")
        (field (name "TOLERANCE") "1%")
        (field (name "АВТОР") "rreali")
      )
      (libsource (lib "Hydrolib") (part "Resistor"))
    )
    (comp (ref "R37")
      (value "1,0 к")
      (footprint "0402R")
      (description "Резистор номиналом 1,0 кОм 1%")
      (fields
        (field (name "PART NUMBER") "Resistor_1.0k_1_0402")
        (field (name "TOLERANCE") "1%")
        (field (name "АВТОР") "rreali")
      )
      (libsource (lib "Hydrolib") (part "Resistor"))
    )
    (comp (ref "R38")
      (value "1,0 к")
      (footprint "0402R")
      (description "Резистор номиналом 1,0 кОм 1%")
      (fields
        (field (name "PART NUMBER") "Resistor_1.0k_1_0402")
        (field (name "TOLERANCE") "1%")
        (field (name "АВТОР") "rreali")
      )
      (libsource (lib "Hydrolib") (part "Resistor"))
    )
    (comp (ref "R39")
      (value "1,0 к")
      (footprint "0402R")
      (description "Резистор номиналом 1,0 кОм 1%")
      (fields
        (field (name "PART NUMBER") "Resistor_1.0k_1_0402")
        (field (name "TOLERANCE") "1%")
        (field (name "АВТОР") "rreali")
      )
      (libsource (lib "Hydrolib") (part "Resistor"))
    )
    (comp (ref "R40")
      (value "470")
      (footprint "0402R")
      (description "Резистор номиналом 470 Ом 1%")
      (fields
        (field (name "PART NUMBER") "Resistor_470_1_0402")
        (field (name "TOLERANCE") "1%")
        (field (name "АВТОР") "rreali")
      )
      (libsource (lib "Hydrolib") (part "Resistor"))
    )
    (comp (ref "R41")
      (value "470")
      (footprint "0402R")
      (description "Резистор номиналом 470 Ом 1%")
      (fields
        (field (name "PART NUMBER") "Resistor_470_1_0402")
        (field (name "TOLERANCE") "1%")
        (field (name "АВТОР") "rreali")
      )
      (libsource (lib "Hydrolib") (part "Resistor"))
    )
    (comp (ref "R42")
      (value "470")
      (footprint "0402R")
      (description "Резистор номиналом 470 Ом 1%")
      (fields
        (field (name "PART NUMBER") "Resistor_470_1_0402")
        (field (name "TOLERANCE") "1%")
        (field (name "АВТОР") "rreali")
      )
      (libsource (lib "Hydrolib") (part "Resistor"))
    )
    (comp (ref "R43")
      (value "470")
      (footprint "0402R")
      (description "Резистор номиналом 470 Ом 1%")
      (fields
        (field (name "PART NUMBER") "Resistor_470_1_0402")
        (field (name "TOLERANCE") "1%")
        (field (name "АВТОР") "rreali")
      )
      (libsource (lib "Hydrolib") (part "Resistor"))
    )
    (comp (ref "R44")
      (value "470")
      (footprint "0402R")
      (description "Резистор номиналом 470 Ом 1%")
      (fields
        (field (name "PART NUMBER") "Resistor_470_1_0402")
        (field (name "TOLERANCE") "1%")
        (field (name "АВТОР") "rreali")
      )
      (libsource (lib "Hydrolib") (part "Resistor"))
    )
    (comp (ref "R45")
      (value "470")
      (footprint "0402R")
      (description "Резистор номиналом 470 Ом 1%")
      (fields
        (field (name "PART NUMBER") "Resistor_470_1_0402")
        (field (name "TOLERANCE") "1%")
        (field (name "АВТОР") "rreali")
      )
      (libsource (lib "Hydrolib") (part "Resistor"))
    )
    (comp (ref "R46")
      (value "470")
      (footprint "0402R")
      (description "Резистор номиналом 470 Ом 1%")
      (fields
        (field (name "PART NUMBER") "Resistor_470_1_0402")
        (field (name "TOLERANCE") "1%")
        (field (name "АВТОР") "rreali")
      )
      (libsource (lib "Hydrolib") (part "Resistor"))
    )
    (comp (ref "R47")
      (value "470")
      (footprint "0402R")
      (description "Резистор номиналом 470 Ом 1%")
      (fields
        (field (name "PART NUMBER") "Resistor_470_1_0402")
        (field (name "TOLERANCE") "1%")
        (field (name "АВТОР") "rreali")
      )
      (libsource (lib "Hydrolib") (part "Resistor"))
    )
    (comp (ref "S1")
      (value "Tact_button")
      (footprint "Button_SMD_6x6")
      (description "Тактовая кнопка")
      (libsource (lib "Hydrolib") (part "Tact_button"))
    )
    (comp (ref "XS1")
      (value "JK0-0136NL")
      (footprint "JK00136NL")
      (description "Модульный разъем (с трансформатором) Cat5/6, RJ45, Гнездо,  1 порт")
      (fields (field (name "MF") "Pulse Electronics") (field (name "АВТОР") "rreali"))
      (libsource (lib "Hydrolib") (part "JK0-0136NL"))
    )
    (comp (ref "XS2")
      (value "JK0-0136NL")
      (footprint "JK00136NL")
      (description "Модульный разъем (с трансформатором) Cat5/6, RJ45, Гнездо,  1 порт")
      (fields (field (name "MF") "Pulse Electronics") (field (name "АВТОР") "rreali"))
      (libsource (lib "Hydrolib") (part "JK0-0136NL"))
    )
    (comp (ref "XS3")
      (value "JK0-0136NL")
      (footprint "JK00136NL")
      (description "Модульный разъем (с трансформатором) Cat5/6, RJ45, Гнездо,  1 порт")
      (fields (field (name "MF") "Pulse Electronics") (field (name "АВТОР") "rreali"))
      (libsource (lib "Hydrolib") (part "JK0-0136NL"))
    )
    (comp (ref "XS4")
      (value "JK0-0136NL")
      (footprint "JK00136NL")
      (description "Модульный разъем (с трансформатором) Cat5/6, RJ45, Гнездо,  1 порт")
      (fields (field (name "MF") "Pulse Electronics") (field (name "АВТОР") "rreali"))
      (libsource (lib "Hydrolib") (part "JK0-0136NL"))
    )
    (comp (ref "ZQ1")
      (value "X322525MOB4SI")
      (footprint "X322525MOB4SI")
      (description "Кварцевый резонатор SMD 25 МГц ±10ppm SMD-3225_4P")
      (fields (field (name "АВТОР") "rreali"))
      (libsource (lib "Hydrolib") (part "XTAL_1-3_GND"))
    )
  )
  (nets
    (net (code "1") (name "+1.1") (class "Default")
      (node (ref "C1") (pin "2") (pinfunction "2_2") (pintype "passive"))
      (node (ref "C10") (pin "2") (pinfunction "2_2") (pintype "passive"))
      (node (ref "C14") (pin "2") (pinfunction "2_2") (pintype "passive"))
      (node (ref "C18") (pin "2") (pinfunction "2_2") (pintype "passive"))
      (node (ref "C22") (pin "2") (pinfunction "2_2") (pintype "passive"))
      (node (ref "C25") (pin "2") (pinfunction "2_2") (pintype "passive"))
      (node (ref "C28") (pin "2") (pinfunction "2_2") (pintype "passive"))
      (node (ref "C35") (pin "2") (pinfunction "2_2") (pintype "passive"))
      (node (ref "C37") (pin "2") (pinfunction "2_2") (pintype "passive"))
      (node (ref "C38") (pin "2") (pinfunction "2_2") (pintype "passive"))
      (node (ref "C39") (pin "2") (pinfunction "2_2") (pintype "passive"))
      (node (ref "C4") (pin "2") (pinfunction "2_2") (pintype "passive"))
      (node (ref "C40") (pin "2") (pinfunction "2_2") (pintype "passive"))
      (node (ref "C42") (pin "2") (pinfunction "2_2") (pintype "passive"))
      (node (ref "C7") (pin "2") (pinfunction "2_2") (pintype "passive"))
      (node (ref "DD1") (pin "101") (pinfunction "AVDDL_101") (pintype "passive"))
      (node (ref "DD1") (pin "111") (pinfunction "AVDDL_111") (pintype "passive"))
      (node (ref "DD1") (pin "116") (pinfunction "PLLVDDL0_116") (pintype "passive"))
      (node (ref "DD1") (pin "124") (pinfunction "AVDDL_124") (pintype "passive"))
      (node (ref "DD1") (pin "14") (pinfunction "AVDDL_14") (pintype "passive"))
      (node (ref "DD1") (pin "21") (pinfunction "DVDDL_21") (pintype "passive"))
      (node (ref "DD1") (pin "28") (pinfunction "AVDDL_28") (pintype "passive"))
      (node (ref "DD1") (pin "34") (pinfunction "PLLVDDL1_34") (pintype "passive"))
      (node (ref "DD1") (pin "53") (pinfunction "DVDDL_53") (pintype "passive"))
      (node (ref "DD1") (pin "6") (pinfunction "AVDDL_6") (pintype "passive"))
      (node (ref "DD1") (pin "71") (pinfunction "DVDDL_71") (pintype "passive"))
      (node (ref "DD1") (pin "87") (pinfunction "DVDDL_87") (pintype "passive"))
      (node (ref "L2") (pin "3") (pinfunction "3_3") (pintype "passive"))
      (node (ref "R22") (pin "2") (pinfunction "2_2") (pintype "passive"))
    )
    (net (code "2") (name "+3.3") (class "Default")
      (node (ref "C11") (pin "2") (pinfunction "2_2") (pintype "passive"))
      (node (ref "C12") (pin "2") (pinfunction "2_2") (pintype "passive"))
      (node (ref "C15") (pin "2") (pinfunction "2_2") (pintype "passive"))
      (node (ref "C16") (pin "2") (pinfunction "2_2") (pintype "passive"))
      (node (ref "C19") (pin "2") (pinfunction "2_2") (pintype "passive"))
      (node (ref "C2") (pin "2") (pinfunction "2_2") (pintype "passive"))
      (node (ref "C20") (pin "2") (pinfunction "2_2") (pintype "passive"))
      (node (ref "C23") (pin "2") (pinfunction "2_2") (pintype "passive"))
      (node (ref "C24") (pin "2") (pinfunction "2_2") (pintype "passive"))
      (node (ref "C26") (pin "2") (pinfunction "2_2") (pintype "passive"))
      (node (ref "C3") (pin "2") (pinfunction "2_2") (pintype "passive"))
      (node (ref "C31") (pin "2") (pinfunction "2_2") (pintype "passive"))
      (node (ref "C33") (pin "2") (pinfunction "2_2") (pintype "passive"))
      (node (ref "C34") (pin "2") (pinfunction "2_2") (pintype "passive"))
      (node (ref "C36") (pin "2") (pinfunction "2_2") (pintype "passive"))
      (node (ref "C43") (pin "2") (pinfunction "2_2") (pintype "passive"))
      (node (ref "C5") (pin "2") (pinfunction "2_2") (pintype "passive"))
      (node (ref "C6") (pin "2") (pinfunction "2_2") (pintype "passive"))
      (node (ref "C8") (pin "2") (pinfunction "2_2") (pintype "passive"))
      (node (ref "C9") (pin "2") (pinfunction "2_2") (pintype "passive"))
      (node (ref "DD1") (pin "1") (pinfunction "AVDDH_1") (pintype "passive"))
      (node (ref "DD1") (pin "106") (pinfunction "AVDDH_106") (pintype "passive"))
      (node (ref "DD1") (pin "11") (pinfunction "AVDDH_11") (pintype "passive"))
      (node (ref "DD1") (pin "119") (pinfunction "AVDDH_119") (pintype "passive"))
      (node (ref "DD1") (pin "17") (pinfunction "AVDDH_17") (pintype "passive"))
      (node (ref "DD1") (pin "18") (pinfunction "DVDDIO_18") (pintype "passive"))
      (node (ref "DD1") (pin "23") (pinfunction "AVDDH_23") (pintype "passive"))
      (node (ref "DD1") (pin "33") (pinfunction "AVDDH_33") (pintype "passive"))
      (node (ref "DD1") (pin "36") (pinfunction "AVDDH_36") (pintype "passive"))
      (node (ref "DD1") (pin "39") (pinfunction "DVDDIO_2_39") (pintype "passive"))
      (node (ref "DD1") (pin "54") (pinfunction "DVDDIO_2_54") (pintype "passive"))
      (node (ref "DD1") (pin "55") (pinfunction "DVDDIO_1_55") (pintype "passive"))
      (node (ref "DD1") (pin "69") (pinfunction "DVDDIO_1_69") (pintype "passive"))
      (node (ref "DD1") (pin "70") (pinfunction "DVDDIO_70") (pintype "passive"))
      (node (ref "DD1") (pin "88") (pinfunction "AVDDH_88") (pintype "passive"))
      (node (ref "DD1") (pin "96") (pinfunction "AVDDH_96") (pintype "passive"))
      (node (ref "L1") (pin "2") (pinfunction "2_2") (pintype "passive"))
      (node (ref "R1") (pin "2") (pinfunction "2_2") (pintype "passive"))
      (node (ref "R11") (pin "2") (pinfunction "2_2") (pintype "passive"))
      (node (ref "R13") (pin "2") (pinfunction "2_2") (pintype "passive"))
      (node (ref "R14") (pin "2") (pinfunction "2_2") (pintype "passive"))
      (node (ref "R15") (pin "2") (pinfunction "2_2") (pintype "passive"))
      (node (ref "R16") (pin "2") (pinfunction "2_2") (pintype "passive"))
      (node (ref "R18") (pin "2") (pinfunction "2_2") (pintype "passive"))
      (node (ref "R2") (pin "2") (pinfunction "2_2") (pintype "passive"))
      (node (ref "R20") (pin "2") (pinfunction "2_2") (pintype "passive"))
      (node (ref "R3") (pin "2") (pinfunction "2_2") (pintype "passive"))
      (node (ref "R4") (pin "2") (pinfunction "2_2") (pintype "passive"))
      (node (ref "R44") (pin "1") (pinfunction "1_1") (pintype "passive"))
      (node (ref "R46") (pin "1") (pinfunction "1_1") (pintype "passive"))
      (node (ref "R5") (pin "2") (pinfunction "2_2") (pintype "passive"))
      (node (ref "R6") (pin "2") (pinfunction "2_2") (pintype "passive"))
      (node (ref "R7") (pin "2") (pinfunction "2_2") (pintype "passive"))
      (node (ref "R8") (pin "2") (pinfunction "2_2") (pintype "passive"))
      (node (ref "R9") (pin "2") (pinfunction "2_2") (pintype "passive"))
    )
    (net (code "3") (name "+12") (class "Default")
      (node (ref "C17") (pin "2") (pinfunction "2_2") (pintype "passive"))
      (node (ref "C30") (pin "2") (pinfunction "2_2") (pintype "passive"))
      (node (ref "DA1") (pin "2") (pinfunction "EN_2") (pintype "passive"))
      (node (ref "DA1") (pin "3") (pinfunction "VIN_3") (pintype "passive"))
      (node (ref "DA2") (pin "2") (pinfunction "EN_2") (pintype "passive"))
      (node (ref "DA2") (pin "3") (pinfunction "VIN_3") (pintype "passive"))
    )
    (net (code "4") (name "/P0A_N") (class "Default")
      (node (ref "DD1") (pin "98") (pinfunction "P0AN_98") (pintype "passive"))
      (node (ref "XS1") (pin "10") (pinfunction "MD1-_10") (pintype "passive"))
    )
    (net (code "5") (name "/P0A_P") (class "Default")
      (node (ref "DD1") (pin "97") (pinfunction "P0AP_97") (pintype "passive"))
      (node (ref "XS1") (pin "11") (pinfunction "MD1+_11") (pintype "passive"))
    )
    (net (code "6") (name "/P0B_N") (class "Default")
      (node (ref "DD1") (pin "100") (pinfunction "P0BN_100") (pintype "passive"))
      (node (ref "XS1") (pin "5") (pinfunction "MD2-_5") (pintype "passive"))
    )
    (net (code "7") (name "/P0B_P") (class "Default")
      (node (ref "DD1") (pin "99") (pinfunction "P0BP_99") (pintype "passive"))
      (node (ref "XS1") (pin "4") (pinfunction "MD2+_4") (pintype "passive"))
    )
    (net (code "8") (name "/P0C_N") (class "Default")
      (node (ref "DD1") (pin "103") (pinfunction "P0CN_103") (pintype "passive"))
      (node (ref "XS1") (pin "2") (pinfunction "MD3-_2") (pintype "passive"))
    )
    (net (code "9") (name "/P0C_P") (class "Default")
      (node (ref "DD1") (pin "102") (pinfunction "P0CP_102") (pintype "passive"))
      (node (ref "XS1") (pin "3") (pinfunction "MD3+_3") (pintype "passive"))
    )
    (net (code "10") (name "/P0D_N") (class "Default")
      (node (ref "DD1") (pin "105") (pinfunction "P0DN_105") (pintype "passive"))
      (node (ref "XS1") (pin "9") (pinfunction "MD4-_9") (pintype "passive"))
    )
    (net (code "11") (name "/P0D_P") (class "Default")
      (node (ref "DD1") (pin "104") (pinfunction "P0DP_104") (pintype "passive"))
      (node (ref "XS1") (pin "8") (pinfunction "MD4+_8") (pintype "passive"))
    )
    (net (code "12") (name "/P0LED0") (class "Default")
      (node (ref "DD1") (pin "75") (pinfunction "P3LED1_75") (pintype "passive"))
      (node (ref "R4") (pin "1") (pinfunction "1_1") (pintype "passive"))
      (node (ref "XS1") (pin "13") (pinfunction "LED_GRN-_13") (pintype "passive"))
    )
    (net (code "13") (name "/P0LED1") (class "Default")
      (node (ref "DD1") (pin "76") (pinfunction "P3LED2_76") (pintype "passive"))
      (node (ref "R5") (pin "1") (pinfunction "1_1") (pintype "passive"))
      (node (ref "XS1") (pin "15") (pinfunction "LED_YELLOW+_15") (pintype "passive"))
    )
    (net (code "14") (name "/P0LED2") (class "Default")
      (node (ref "DD1") (pin "77") (pinfunction "P3LED0_77") (pintype "passive"))
      (node (ref "R10") (pin "2") (pinfunction "2_2") (pintype "passive"))
      (node (ref "R40") (pin "1") (pinfunction "1_1") (pintype "passive"))
    )
    (net (code "15") (name "/P1A_N") (class "Default")
      (node (ref "DD1") (pin "108") (pinfunction "P1AN_108") (pintype "passive"))
      (node (ref "XS2") (pin "10") (pinfunction "MD1-_10") (pintype "passive"))
    )
    (net (code "16") (name "/P1A_P") (class "Default")
      (node (ref "DD1") (pin "107") (pinfunction "P1AP_107") (pintype "passive"))
      (node (ref "XS2") (pin "11") (pinfunction "MD1+_11") (pintype "passive"))
    )
    (net (code "17") (name "/P1B_N") (class "Default")
      (node (ref "DD1") (pin "110") (pinfunction "P1BN_110") (pintype "passive"))
      (node (ref "XS2") (pin "5") (pinfunction "MD2-_5") (pintype "passive"))
    )
    (net (code "18") (name "/P1B_P") (class "Default")
      (node (ref "DD1") (pin "109") (pinfunction "P1BP_109") (pintype "passive"))
      (node (ref "XS2") (pin "4") (pinfunction "MD2+_4") (pintype "passive"))
    )
    (net (code "19") (name "/P1C_N") (class "Default")
      (node (ref "DD1") (pin "113") (pinfunction "P1CN_113") (pintype "passive"))
      (node (ref "XS2") (pin "2") (pinfunction "MD3-_2") (pintype "passive"))
    )
    (net (code "20") (name "/P1C_P") (class "Default")
      (node (ref "DD1") (pin "112") (pinfunction "P1CP_112") (pintype "passive"))
      (node (ref "XS2") (pin "3") (pinfunction "MD3+_3") (pintype "passive"))
    )
    (net (code "21") (name "/P1D_N") (class "Default")
      (node (ref "DD1") (pin "115") (pinfunction "P1DN_115") (pintype "passive"))
      (node (ref "XS2") (pin "9") (pinfunction "MD4-_9") (pintype "passive"))
    )
    (net (code "22") (name "/P1D_P") (class "Default")
      (node (ref "DD1") (pin "114") (pinfunction "P1DP_114") (pintype "passive"))
      (node (ref "XS2") (pin "8") (pinfunction "MD4+_8") (pintype "passive"))
    )
    (net (code "23") (name "/P1LED0") (class "Default")
      (node (ref "DD1") (pin "79") (pinfunction "P2LED0/DISAUTOLOAD_79") (pintype "passive"))
      (node (ref "R45") (pin "1") (pinfunction "1_1") (pintype "passive"))
      (node (ref "R8") (pin "1") (pinfunction "1_1") (pintype "passive"))
    )
    (net (code "24") (name "/P1LED1") (class "Default")
      (node (ref "DD1") (pin "78") (pinfunction "P2LED2/DIS_8051_78") (pintype "passive"))
      (node (ref "R7") (pin "1") (pinfunction "1_1") (pintype "passive"))
      (node (ref "XS2") (pin "15") (pinfunction "LED_YELLOW+_15") (pintype "passive"))
    )
    (net (code "25") (name "/P1LED2") (class "Default")
      (node (ref "DD1") (pin "80") (pinfunction "P2LED1_80") (pintype "passive"))
      (node (ref "R41") (pin "1") (pinfunction "1_1") (pintype "passive"))
      (node (ref "R9") (pin "1") (pinfunction "1_1") (pintype "passive"))
    )
    (net (code "26") (name "/P2A_N") (class "Default")
      (node (ref "DD1") (pin "121") (pinfunction "P2AN_121") (pintype "passive"))
      (node (ref "XS3") (pin "10") (pinfunction "MD1-_10") (pintype "passive"))
    )
    (net (code "27") (name "/P2A_P") (class "Default")
      (node (ref "DD1") (pin "120") (pinfunction "P2AP_120") (pintype "passive"))
      (node (ref "XS3") (pin "11") (pinfunction "MD1+_11") (pintype "passive"))
    )
    (net (code "28") (name "/P2B_N") (class "Default")
      (node (ref "DD1") (pin "123") (pinfunction "P2BN_123") (pintype "passive"))
      (node (ref "XS3") (pin "5") (pinfunction "MD2-_5") (pintype "passive"))
    )
    (net (code "29") (name "/P2B_P") (class "Default")
      (node (ref "DD1") (pin "122") (pinfunction "P2BP_122") (pintype "passive"))
      (node (ref "XS3") (pin "4") (pinfunction "MD2+_4") (pintype "passive"))
    )
    (net (code "30") (name "/P2C_N") (class "Default")
      (node (ref "DD1") (pin "126") (pinfunction "P2CN_126") (pintype "passive"))
      (node (ref "XS3") (pin "2") (pinfunction "MD3-_2") (pintype "passive"))
    )
    (net (code "31") (name "/P2C_P") (class "Default")
      (node (ref "DD1") (pin "125") (pinfunction "P2CP_125") (pintype "passive"))
      (node (ref "XS3") (pin "3") (pinfunction "MD3+_3") (pintype "passive"))
    )
    (net (code "32") (name "/P2D_N") (class "Default")
      (node (ref "DD1") (pin "128") (pinfunction "P2DN_128") (pintype "passive"))
      (node (ref "XS3") (pin "9") (pinfunction "MD4-_9") (pintype "passive"))
    )
    (net (code "33") (name "/P2D_P") (class "Default")
      (node (ref "DD1") (pin "127") (pinfunction "P2DP_127") (pintype "passive"))
      (node (ref "XS3") (pin "8") (pinfunction "MD4+_8") (pintype "passive"))
    )
    (net (code "34") (name "/P2LED0") (class "Default")
      (node (ref "DD1") (pin "82") (pinfunction "P1LED0_82") (pintype "passive"))
      (node (ref "R12") (pin "2") (pinfunction "2_2") (pintype "passive"))
      (node (ref "XS3") (pin "13") (pinfunction "LED_GRN-_13") (pintype "passive"))
    )
    (net (code "35") (name "/P2LED1") (class "Default")
      (node (ref "DD1") (pin "81") (pinfunction "P1LED2_81") (pintype "passive"))
      (node (ref "R11") (pin "1") (pinfunction "1_1") (pintype "passive"))
      (node (ref "XS3") (pin "15") (pinfunction "LED_YELLOW+_15") (pintype "passive"))
    )
    (net (code "36") (name "/P2LED2") (class "Default")
      (node (ref "DD1") (pin "83") (pinfunction "P1LED1_83") (pintype "passive"))
      (node (ref "R13") (pin "1") (pinfunction "1_1") (pintype "passive"))
      (node (ref "R42") (pin "1") (pinfunction "1_1") (pintype "passive"))
    )
    (net (code "37") (name "/P3A_N") (class "Default")
      (node (ref "DD1") (pin "3") (pinfunction "P3AN_3") (pintype "passive"))
      (node (ref "XS4") (pin "10") (pinfunction "MD1-_10") (pintype "passive"))
    )
    (net (code "38") (name "/P3A_P") (class "Default")
      (node (ref "DD1") (pin "2") (pinfunction "P3AP_2") (pintype "passive"))
      (node (ref "XS4") (pin "11") (pinfunction "MD1+_11") (pintype "passive"))
    )
    (net (code "39") (name "/P3B_N") (class "Default")
      (node (ref "DD1") (pin "5") (pinfunction "P3BN_5") (pintype "passive"))
      (node (ref "XS4") (pin "5") (pinfunction "MD2-_5") (pintype "passive"))
    )
    (net (code "40") (name "/P3B_P") (class "Default")
      (node (ref "DD1") (pin "4") (pinfunction "P3BP_4") (pintype "passive"))
      (node (ref "XS4") (pin "4") (pinfunction "MD2+_4") (pintype "passive"))
    )
    (net (code "41") (name "/P3C_N") (class "Default")
      (node (ref "DD1") (pin "8") (pinfunction "P3CN_8") (pintype "passive"))
      (node (ref "XS4") (pin "2") (pinfunction "MD3-_2") (pintype "passive"))
    )
    (net (code "42") (name "/P3C_P") (class "Default")
      (node (ref "DD1") (pin "7") (pinfunction "P3CP_7") (pintype "passive"))
      (node (ref "XS4") (pin "3") (pinfunction "MD3+_3") (pintype "passive"))
    )
    (net (code "43") (name "/P3D_N") (class "Default")
      (node (ref "DD1") (pin "10") (pinfunction "P3DN_10") (pintype "passive"))
      (node (ref "XS4") (pin "9") (pinfunction "MD4-_9") (pintype "passive"))
    )
    (net (code "44") (name "/P3D_P") (class "Default")
      (node (ref "DD1") (pin "9") (pinfunction "P3DP_9") (pintype "passive"))
      (node (ref "XS4") (pin "8") (pinfunction "MD4+_8") (pintype "passive"))
    )
    (net (code "45") (name "/P3LED0") (class "Default")
      (node (ref "DD1") (pin "84") (pinfunction "P0LED2/EN_PHY_84") (pintype "passive"))
      (node (ref "R14") (pin "1") (pinfunction "1_1") (pintype "passive"))
      (node (ref "R47") (pin "1") (pinfunction "1_1") (pintype "passive"))
    )
    (net (code "46") (name "/P3LED1") (class "Default")
      (node (ref "DD1") (pin "86") (pinfunction "P0LED0/LED_CK/SMI_SEL_86") (pintype "passive"))
      (node (ref "R16") (pin "1") (pinfunction "1_1") (pintype "passive"))
      (node (ref "XS4") (pin "15") (pinfunction "LED_YELLOW+_15") (pintype "passive"))
    )
    (net (code "47") (name "/P3LED2") (class "Default")
      (node (ref "DD1") (pin "85") (pinfunction "P0LED1/LED_DA_85") (pintype "passive"))
      (node (ref "R15") (pin "1") (pinfunction "1_1") (pintype "passive"))
      (node (ref "R43") (pin "1") (pinfunction "1_1") (pintype "passive"))
    )
    (net (code "48") (name "GND") (class "Default")
      (node (ref "C1") (pin "1") (pinfunction "1_1") (pintype "passive"))
      (node (ref "C10") (pin "1") (pinfunction "1_1") (pintype "passive"))
      (node (ref "C11") (pin "1") (pinfunction "1_1") (pintype "passive"))
      (node (ref "C12") (pin "1") (pinfunction "1_1") (pintype "passive"))
      (node (ref "C13") (pin "1") (pinfunction "1_1") (pintype "passive"))
      (node (ref "C14") (pin "1") (pinfunction "1_1") (pintype "passive"))
      (node (ref "C15") (pin "1") (pinfunction "1_1") (pintype "passive"))
      (node (ref "C16") (pin "1") (pinfunction "1_1") (pintype "passive"))
      (node (ref "C17") (pin "1") (pinfunction "1_1") (pintype "passive"))
      (node (ref "C18") (pin "1") (pinfunction "1_1") (pintype "passive"))
      (node (ref "C19") (pin "1") (pinfunction "1_1") (pintype "passive"))
      (node (ref "C2") (pin "1") (pinfunction "1_1") (pintype "passive"))
      (node (ref "C20") (pin "1") (pinfunction "1_1") (pintype "passive"))
      (node (ref "C21") (pin "1") (pinfunction "1_1") (pintype "passive"))
      (node (ref "C22") (pin "1") (pinfunction "1_1") (pintype "passive"))
      (node (ref "C23") (pin "1") (pinfunction "1_1") (pintype "passive"))
      (node (ref "C24") (pin "1") (pinfunction "1_1") (pintype "passive"))
      (node (ref "C25") (pin "1") (pinfunction "1_1") (pintype "passive"))
      (node (ref "C26") (pin "1") (pinfunction "1_1") (pintype "passive"))
      (node (ref "C27") (pin "2") (pinfunction "2_2") (pintype "passive"))
      (node (ref "C28") (pin "1") (pinfunction "1_1") (pintype "passive"))
      (node (ref "C3") (pin "1") (pinfunction "1_1") (pintype "passive"))
      (node (ref "C30") (pin "1") (pinfunction "1_1") (pintype "passive"))
      (node (ref "C33") (pin "1") (pinfunction "1_1") (pintype "passive"))
      (node (ref "C34") (pin "1") (pinfunction "1_1") (pintype "passive"))
      (node (ref "C36") (pin "1") (pinfunction "1_1") (pintype "passive"))
      (node (ref "C37") (pin "1") (pinfunction "1_1") (pintype "passive"))
      (node (ref "C38") (pin "1") (pinfunction "1_1") (pintype "passive"))
      (node (ref "C39") (pin "1") (pinfunction "1_1") (pintype "passive"))
      (node (ref "C4") (pin "1") (pinfunction "1_1") (pintype "passive"))
      (node (ref "C40") (pin "1") (pinfunction "1_1") (pintype "passive"))
      (node (ref "C41") (pin "1") (pinfunction "1_1") (pintype "passive"))
      (node (ref "C42") (pin "1") (pinfunction "1_1") (pintype "passive"))
      (node (ref "C43") (pin "1") (pinfunction "1_1") (pintype "passive"))
      (node (ref "C44") (pin "2") (pinfunction "2_2") (pintype "passive"))
      (node (ref "C45") (pin "2") (pinfunction "2_2") (pintype "passive"))
      (node (ref "C46") (pin "2") (pinfunction "2_2") (pintype "passive"))
      (node (ref "C47") (pin "2") (pinfunction "2_2") (pintype "passive"))
      (node (ref "C5") (pin "1") (pinfunction "1_1") (pintype "passive"))
      (node (ref "C6") (pin "1") (pinfunction "1_1") (pintype "passive"))
      (node (ref "C7") (pin "1") (pinfunction "1_1") (pintype "passive"))
      (node (ref "C8") (pin "1") (pinfunction "1_1") (pintype "passive"))
      (node (ref "C9") (pin "1") (pinfunction "1_1") (pintype "passive"))
      (node (ref "DA1") (pin "4") (pinfunction "GND_4") (pintype "passive"))
      (node (ref "DA2") (pin "4") (pinfunction "GND_4") (pintype "passive"))
      (node (ref "R10") (pin "1") (pinfunction "1_1") (pintype "passive"))
      (node (ref "R12") (pin "1") (pinfunction "1_1") (pintype "passive"))
      (node (ref "R17") (pin "1") (pinfunction "1_1") (pintype "passive"))
      (node (ref "R19") (pin "1") (pinfunction "1_1") (pintype "passive"))
      (node (ref "R21") (pin "1") (pinfunction "1_1") (pintype "passive"))
      (node (ref "R23") (pin "1") (pinfunction "1_1") (pintype "passive"))
      (node (ref "R24") (pin "1") (pinfunction "1_1") (pintype "passive"))
      (node (ref "R25") (pin "1") (pinfunction "1_1") (pintype "passive"))
      (node (ref "R26") (pin "1") (pinfunction "1_1") (pintype "passive"))
      (node (ref "R27") (pin "1") (pinfunction "1_1") (pintype "passive"))
      (node (ref "R28") (pin "1") (pinfunction "1_1") (pintype "passive"))
      (node (ref "R29") (pin "1") (pinfunction "1_1") (pintype "passive"))
      (node (ref "R30") (pin "1") (pinfunction "1_1") (pintype "passive"))
      (node (ref "R31") (pin "1") (pinfunction "1_1") (pintype "passive"))
      (node (ref "R32") (pin "1") (pinfunction "1_1") (pintype "passive"))
      (node (ref "R33") (pin "1") (pinfunction "1_1") (pintype "passive"))
      (node (ref "R34") (pin "1") (pinfunction "1_1") (pintype "passive"))
      (node (ref "R35") (pin "1") (pinfunction "1_1") (pintype "passive"))
      (node (ref "R36") (pin "1") (pinfunction "1_1") (pintype "passive"))
      (node (ref "R37") (pin "1") (pinfunction "1_1") (pintype "passive"))
      (node (ref "R38") (pin "1") (pinfunction "1_1") (pintype "passive"))
      (node (ref "R39") (pin "1") (pinfunction "1_1") (pintype "passive"))
      (node (ref "S1") (pin "2") (pinfunction "2_2") (pintype "passive"))
      (node (ref "XS2") (pin "13") (pinfunction "LED_GRN-_13") (pintype "passive"))
      (node (ref "XS4") (pin "13") (pinfunction "LED_GRN-_13") (pintype "passive"))
      (node (ref "ZQ1") (pin "2") (pinfunction "GND_2") (pintype "passive"))
      (node (ref "ZQ1") (pin "4") (pinfunction "GND_4") (pintype "passive"))
    )
    (net (code "49") (name "GND_ETH") (class "Default")
      (node (ref "C41") (pin "2") (pinfunction "2_2") (pintype "passive"))
      (node (ref "R33") (pin "2") (pinfunction "2_2") (pintype "passive"))
      (node (ref "XS1") (pin "0") (pinfunction "Корпус_0") (pintype "passive"))
      (node (ref "XS2") (pin "0") (pinfunction "Корпус_0") (pintype "passive"))
      (node (ref "XS3") (pin "0") (pinfunction "Корпус_0") (pintype "passive"))
      (node (ref "XS4") (pin "0") (pinfunction "Корпус_0") (pintype "passive"))
    )
    (net (code "50") (name "Net-(DA1-BST)") (class "Default")
      (node (ref "C29") (pin "1") (pinfunction "1_1") (pintype "passive"))
      (node (ref "DA1") (pin "6") (pinfunction "BST_6") (pintype "passive"))
    )
    (net (code "51") (name "Net-(DA1-FB)") (class "Default")
      (node (ref "C31") (pin "1") (pinfunction "1_1") (pintype "passive"))
      (node (ref "DA1") (pin "1") (pinfunction "FB_1") (pintype "passive"))
      (node (ref "R20") (pin "1") (pinfunction "1_1") (pintype "passive"))
      (node (ref "R21") (pin "2") (pinfunction "2_2") (pintype "passive"))
    )
    (net (code "52") (name "Net-(DA1-SW)") (class "Default")
      (node (ref "C29") (pin "2") (pinfunction "2_2") (pintype "passive"))
      (node (ref "DA1") (pin "5") (pinfunction "SW_5") (pintype "passive"))
      (node (ref "L1") (pin "1") (pinfunction "1_1") (pintype "passive"))
    )
    (net (code "53") (name "Net-(DA2-BST)") (class "Default")
      (node (ref "C32") (pin "1") (pinfunction "1_1") (pintype "passive"))
      (node (ref "DA2") (pin "6") (pinfunction "BST_6") (pintype "passive"))
    )
    (net (code "54") (name "Net-(DA2-FB)") (class "Default")
      (node (ref "C35") (pin "1") (pinfunction "1_1") (pintype "passive"))
      (node (ref "DA2") (pin "1") (pinfunction "FB_1") (pintype "passive"))
      (node (ref "R22") (pin "1") (pinfunction "1_1") (pintype "passive"))
      (node (ref "R23") (pin "2") (pinfunction "2_2") (pintype "passive"))
    )
    (net (code "55") (name "Net-(DA2-SW)") (class "Default")
      (node (ref "C32") (pin "2") (pinfunction "2_2") (pintype "passive"))
      (node (ref "DA2") (pin "5") (pinfunction "SW_5") (pintype "passive"))
      (node (ref "L2") (pin "1") (pinfunction "1_1") (pintype "passive"))
    )
    (net (code "56") (name "Net-(DD1-DIS_LPD{slash}BUZZER)") (class "Default")
      (node (ref "DD1") (pin "20") (pinfunction "DIS_LPD/BUZZER_20") (pintype "passive"))
      (node (ref "R18") (pin "1") (pinfunction "1_1") (pintype "passive"))
    )
    (net (code "57") (name "Net-(DD1-M1M_CRS)") (class "Default")
      (node (ref "DD1") (pin "56") (pinfunction "M1M_CRS_56") (pintype "passive"))
      (node (ref "R31") (pin "2") (pinfunction "2_2") (pintype "passive"))
    )
    (net (code "58") (name "Net-(DD1-MDIREF)") (class "Default")
      (node (ref "DD1") (pin "13") (pinfunction "MDIREF_13") (pintype "passive"))
      (node (ref "R17") (pin "2") (pinfunction "2_2") (pintype "passive"))
    )
    (net (code "59") (name "Net-(DD1-P4LED0{slash}EEPROM_MOD)") (class "Default")
      (node (ref "DD1") (pin "73") (pinfunction "P4LED0/EEPROM_MOD_73") (pintype "passive"))
      (node (ref "R2") (pin "1") (pinfunction "1_1") (pintype "passive"))
    )
    (net (code "60") (name "Net-(DD1-P4LED1)") (class "Default")
      (node (ref "DD1") (pin "74") (pinfunction "P4LED1_74") (pintype "passive"))
      (node (ref "R3") (pin "1") (pinfunction "1_1") (pintype "passive"))
    )
    (net (code "61") (name "Net-(DD1-P4LED2{slash}DIS_SPIS)") (class "Default")
      (node (ref "DD1") (pin "72") (pinfunction "P4LED2/DIS_SPIS_72") (pintype "passive"))
      (node (ref "R1") (pin "1") (pinfunction "1_1") (pintype "passive"))
    )
    (net (code "62") (name "Net-(DD1-RESERVED-Pad40)") (class "Default")
      (node (ref "DD1") (pin "40") (pinfunction "RESERVED_40") (pintype "passive"))
      (node (ref "R19") (pin "2") (pinfunction "2_2") (pintype "passive"))
    )
    (net (code "63") (name "Net-(DD1-RG1_RXCLK{slash}M1M_RXCLK{slash}M1P_TXCLK)") (class "Default")
      (node (ref "DD1") (pin "63") (pinfunction "RG1_RXCLK/M1M_RXCLK/M1P_TXCLK_63") (pintype "passive"))
      (node (ref "R29") (pin "2") (pinfunction "2_2") (pintype "passive"))
    )
    (net (code "64") (name "Net-(DD1-RG1_RXCTL{slash}M1M_RXDV{slash}M1P_TXEN)") (class "Default")
      (node (ref "DD1") (pin "64") (pinfunction "RG1_RXCTL/M1M_RXDV/M1P_TXEN_64") (pintype "passive"))
      (node (ref "R28") (pin "2") (pinfunction "2_2") (pintype "passive"))
    )
    (net (code "65") (name "Net-(DD1-RG1_RXD0{slash}M1M_RXD0{slash}M1P_TXD0)") (class "Default")
      (node (ref "DD1") (pin "65") (pinfunction "RG1_RXD0/M1M_RXD0/M1P_TXD0_65") (pintype "passive"))
      (node (ref "R27") (pin "2") (pinfunction "2_2") (pintype "passive"))
    )
    (net (code "66") (name "Net-(DD1-RG1_RXD1{slash}M1M_RXD1{slash}M1P_TXD1)") (class "Default")
      (node (ref "DD1") (pin "66") (pinfunction "RG1_RXD1/M1M_RXD1/M1P_TXD1_66") (pintype "passive"))
      (node (ref "R26") (pin "2") (pinfunction "2_2") (pintype "passive"))
    )
    (net (code "67") (name "Net-(DD1-RG1_RXD2{slash}M1M_RXD2{slash}M1P_TXD2)") (class "Default")
      (node (ref "DD1") (pin "67") (pinfunction "RG1_RXD2/M1M_RXD2/M1P_TXD2_67") (pintype "passive"))
      (node (ref "R25") (pin "2") (pinfunction "2_2") (pintype "passive"))
    )
    (net (code "68") (name "Net-(DD1-RG1_RXD3{slash}M1M_RXD3{slash}M1P_TXD3)") (class "Default")
      (node (ref "DD1") (pin "68") (pinfunction "RG1_RXD3/M1M_RXD3/M1P_TXD3_68") (pintype "passive"))
      (node (ref "R24") (pin "2") (pinfunction "2_2") (pintype "passive"))
    )
    (net (code "69") (name "Net-(DD1-RG1_TXCLK{slash}M1M_TXCLK{slash}M1P_RXCLK)") (class "Default")
      (node (ref "DD1") (pin "62") (pinfunction "RG1_TXCLK/M1M_TXCLK/M1P_RXCLK_62") (pintype "passive"))
      (node (ref "R30") (pin "2") (pinfunction "2_2") (pintype "passive"))
    )
    (net (code "70") (name "Net-(DD1-RG2_RXCLK{slash}M2M_RXCLK{slash}M2P_TXCLK)") (class "Default")
      (node (ref "DD1") (pin "47") (pinfunction "RG2_RXCLK/M2M_RXCLK/M2P_TXCLK_47") (pintype "passive"))
      (node (ref "R38") (pin "2") (pinfunction "2_2") (pintype "passive"))
    )
    (net (code "71") (name "Net-(DD1-RG2_RXCTL{slash}M2M_RXDV{slash}M2P_TXEN)") (class "Default")
      (node (ref "DD1") (pin "48") (pinfunction "RG2_RXCTL/M2M_RXDV/M2P_TXEN_48") (pintype "passive"))
      (node (ref "R37") (pin "2") (pinfunction "2_2") (pintype "passive"))
    )
    (net (code "72") (name "Net-(DD1-RG2_RXD0{slash}M2M_RXD0{slash}M2P_TXD0)") (class "Default")
      (node (ref "DD1") (pin "49") (pinfunction "RG2_RXD0/M2M_RXD0/M2P_TXD0_49") (pintype "passive"))
      (node (ref "R36") (pin "2") (pinfunction "2_2") (pintype "passive"))
    )
    (net (code "73") (name "Net-(DD1-RG2_RXD1{slash}M2M_RXD1{slash}M2P_TXD1)") (class "Default")
      (node (ref "DD1") (pin "50") (pinfunction "RG2_RXD1/M2M_RXD1/M2P_TXD1_50") (pintype "passive"))
      (node (ref "R35") (pin "2") (pinfunction "2_2") (pintype "passive"))
    )
    (net (code "74") (name "Net-(DD1-RG2_RXD2{slash}M2M_RXD2{slash}M2P_TXD2)") (class "Default")
      (node (ref "DD1") (pin "51") (pinfunction "RG2_RXD2/M2M_RXD2/M2P_TXD2_51") (pintype "passive"))
      (node (ref "R34") (pin "2") (pinfunction "2_2") (pintype "passive"))
    )
    (net (code "75") (name "Net-(DD1-RG2_RXD3{slash}M2M_RXD3{slash}M2P_TXD3)") (class "Default")
      (node (ref "DD1") (pin "52") (pinfunction "RG2_RXD3/M2M_RXD3/M2P_TXD3_52") (pintype "passive"))
      (node (ref "R32") (pin "2") (pinfunction "2_2") (pintype "passive"))
    )
    (net (code "76") (name "Net-(DD1-RG2_TXCLK{slash}M2M_TXCLK{slash}M2P_RXCLK)") (class "Default")
      (node (ref "DD1") (pin "46") (pinfunction "RG2_TXCLK/M2M_TXCLK/M2P_RXCLK_46") (pintype "passive"))
      (node (ref "R39") (pin "2") (pinfunction "2_2") (pintype "passive"))
    )
    (net (code "77") (name "Net-(DD1-XTALI)") (class "Default")
      (node (ref "C21") (pin "2") (pinfunction "2_2") (pintype "passive"))
      (node (ref "DD1") (pin "90") (pinfunction "XTALI_90") (pintype "passive"))
      (node (ref "ZQ1") (pin "1") (pinfunction "1_1") (pintype "passive"))
    )
    (net (code "78") (name "Net-(DD1-XTALO)") (class "Default")
      (node (ref "C27") (pin "1") (pinfunction "1_1") (pintype "passive"))
      (node (ref "DD1") (pin "89") (pinfunction "XTALO_89") (pintype "passive"))
      (node (ref "ZQ1") (pin "3") (pinfunction "3_3") (pintype "passive"))
    )
    (net (code "79") (name "Net-(DD1-nRESET)") (class "Default")
      (node (ref "C13") (pin "2") (pinfunction "2_2") (pintype "passive"))
      (node (ref "DD1") (pin "91") (pinfunction "nRESET_91") (pintype "passive"))
      (node (ref "R6") (pin "1") (pinfunction "1_1") (pintype "passive"))
      (node (ref "S1") (pin "1") (pinfunction "1_1") (pintype "passive"))
    )
    (net (code "80") (name "Net-(XS1-LED_GRN+)") (class "Default")
      (node (ref "R44") (pin "2") (pinfunction "2_2") (pintype "passive"))
      (node (ref "XS1") (pin "14") (pinfunction "LED_GRN+_14") (pintype "passive"))
    )
    (net (code "81") (name "Net-(XS1-LED_YELLOW-)") (class "Default")
      (node (ref "R40") (pin "2") (pinfunction "2_2") (pintype "passive"))
      (node (ref "XS1") (pin "16") (pinfunction "LED_YELLOW-_16") (pintype "passive"))
    )
    (net (code "82") (name "Net-(XS1-MDCT1)") (class "Default")
      (node (ref "C44") (pin "1") (pinfunction "1_1") (pintype "passive"))
      (node (ref "XS1") (pin "1") (pinfunction "MDCT3_1") (pintype "passive"))
      (node (ref "XS1") (pin "12") (pinfunction "MDCT1_12") (pintype "passive"))
      (node (ref "XS1") (pin "6") (pinfunction "MDCT2_6") (pintype "passive"))
      (node (ref "XS1") (pin "7") (pinfunction "MDCT4_7") (pintype "passive"))
    )
    (net (code "83") (name "Net-(XS2-LED_GRN+)") (class "Default")
      (node (ref "R45") (pin "2") (pinfunction "2_2") (pintype "passive"))
      (node (ref "XS2") (pin "14") (pinfunction "LED_GRN+_14") (pintype "passive"))
    )
    (net (code "84") (name "Net-(XS2-LED_YELLOW-)") (class "Default")
      (node (ref "R41") (pin "2") (pinfunction "2_2") (pintype "passive"))
      (node (ref "XS2") (pin "16") (pinfunction "LED_YELLOW-_16") (pintype "passive"))
    )
    (net (code "85") (name "Net-(XS2-MDCT1)") (class "Default")
      (node (ref "C45") (pin "1") (pinfunction "1_1") (pintype "passive"))
      (node (ref "XS2") (pin "1") (pinfunction "MDCT3_1") (pintype "passive"))
      (node (ref "XS2") (pin "12") (pinfunction "MDCT1_12") (pintype "passive"))
      (node (ref "XS2") (pin "6") (pinfunction "MDCT2_6") (pintype "passive"))
      (node (ref "XS2") (pin "7") (pinfunction "MDCT4_7") (pintype "passive"))
    )
    (net (code "86") (name "Net-(XS3-LED_GRN+)") (class "Default")
      (node (ref "R46") (pin "2") (pinfunction "2_2") (pintype "passive"))
      (node (ref "XS3") (pin "14") (pinfunction "LED_GRN+_14") (pintype "passive"))
    )
    (net (code "87") (name "Net-(XS3-LED_YELLOW-)") (class "Default")
      (node (ref "R42") (pin "2") (pinfunction "2_2") (pintype "passive"))
      (node (ref "XS3") (pin "16") (pinfunction "LED_YELLOW-_16") (pintype "passive"))
    )
    (net (code "88") (name "Net-(XS3-MDCT1)") (class "Default")
      (node (ref "C46") (pin "1") (pinfunction "1_1") (pintype "passive"))
      (node (ref "XS3") (pin "1") (pinfunction "MDCT3_1") (pintype "passive"))
      (node (ref "XS3") (pin "12") (pinfunction "MDCT1_12") (pintype "passive"))
      (node (ref "XS3") (pin "6") (pinfunction "MDCT2_6") (pintype "passive"))
      (node (ref "XS3") (pin "7") (pinfunction "MDCT4_7") (pintype "passive"))
    )
    (net (code "89") (name "Net-(XS4-LED_GRN+)") (class "Default")
      (node (ref "R47") (pin "2") (pinfunction "2_2") (pintype "passive"))
      (node (ref "XS4") (pin "14") (pinfunction "LED_GRN+_14") (pintype "passive"))
    )
    (net (code "90") (name "Net-(XS4-LED_YELLOW-)") (class "Default")
      (node (ref "R43") (pin "2") (pinfunction "2_2") (pintype "passive"))
      (node (ref "XS4") (pin "16") (pinfunction "LED_YELLOW-_16") (pintype "passive"))
    )
    (net (code "91") (name "Net-(XS4-MDCT1)") (class "Default")
      (node (ref "C47") (pin "1") (pinfunction "1_1") (pintype "passive"))
      (node (ref "XS4") (pin "1") (pinfunction "MDCT3_1") (pintype "passive"))
      (node (ref "XS4") (pin "12") (pinfunction "MDCT1_12") (pintype "passive"))
      (node (ref "XS4") (pin "6") (pinfunction "MDCT2_6") (pintype "passive"))
      (node (ref "XS4") (pin "7") (pinfunction "MDCT4_7") (pintype "passive"))
    )
    (net (code "92") (name "unconnected-(DD1-AGND-Pad12)") (class "Default")
      (node (ref "DD1") (pin "12") (pinfunction "AGND_12") (pintype "passive"))
    )
    (net (code "93") (name "unconnected-(DD1-ATESTCK0-Pad117)") (class "Default")
      (node (ref "DD1") (pin "117") (pinfunction "ATESTCK0_117") (pintype "passive"))
    )
    (net (code "94") (name "unconnected-(DD1-GND(EPAD)-Pad129)") (class "Default")
      (node (ref "DD1") (pin "129") (pinfunction "GND(EPAD)_129") (pintype "passive"))
    )
    (net (code "95") (name "unconnected-(DD1-INTERRUPT-Pad19)") (class "Default")
      (node (ref "DD1") (pin "19") (pinfunction "INTERRUPT_19") (pintype "passive"))
    )
    (net (code "96") (name "unconnected-(DD1-P4AN-Pad25)") (class "Default")
      (node (ref "DD1") (pin "25") (pinfunction "P4AN_25") (pintype "passive"))
    )
    (net (code "97") (name "unconnected-(DD1-P4AP-Pad24)") (class "Default")
      (node (ref "DD1") (pin "24") (pinfunction "P4AP_24") (pintype "passive"))
    )
    (net (code "98") (name "unconnected-(DD1-P4BN-Pad27)") (class "Default")
      (node (ref "DD1") (pin "27") (pinfunction "P4BN_27") (pintype "passive"))
    )
    (net (code "99") (name "unconnected-(DD1-P4BP-Pad26)") (class "Default")
      (node (ref "DD1") (pin "26") (pinfunction "P4BP_26") (pintype "passive"))
    )
    (net (code "100") (name "unconnected-(DD1-P4CN-Pad30)") (class "Default")
      (node (ref "DD1") (pin "30") (pinfunction "P4CN_30") (pintype "passive"))
    )
    (net (code "101") (name "unconnected-(DD1-P4CP-Pad29)") (class "Default")
      (node (ref "DD1") (pin "29") (pinfunction "P4CP_29") (pintype "passive"))
    )
    (net (code "102") (name "unconnected-(DD1-P4DN-Pad32)") (class "Default")
      (node (ref "DD1") (pin "32") (pinfunction "P4DN_32") (pintype "passive"))
    )
    (net (code "103") (name "unconnected-(DD1-P4DP-Pad31)") (class "Default")
      (node (ref "DD1") (pin "31") (pinfunction "P4DP_31") (pintype "passive"))
    )
    (net (code "104") (name "unconnected-(DD1-PLLGND0-Pad118)") (class "Default")
      (node (ref "DD1") (pin "118") (pinfunction "PLLGND0_118") (pintype "passive"))
    )
    (net (code "105") (name "unconnected-(DD1-RESERVED-Pad22)") (class "Default")
      (node (ref "DD1") (pin "22") (pinfunction "RESERVED_22") (pintype "passive"))
    )
    (net (code "106") (name "unconnected-(DD1-RESERVED-Pad35)") (class "Default")
      (node (ref "DD1") (pin "35") (pinfunction "RESERVED_35") (pintype "passive"))
    )
    (net (code "107") (name "unconnected-(DD1-RESERVED-Pad37)") (class "Default")
      (node (ref "DD1") (pin "37") (pinfunction "RESERVED_37") (pintype "passive"))
    )
    (net (code "108") (name "unconnected-(DD1-RESERVED-Pad38)") (class "Default")
      (node (ref "DD1") (pin "38") (pinfunction "RESERVED_38") (pintype "passive"))
    )
    (net (code "109") (name "unconnected-(DD1-RG1_TXCTL{slash}M1M_TXEN{slash}M1P_RXDV-Pad61)") (class "Default")
      (node (ref "DD1") (pin "61") (pinfunction "RG1_TXCTL/M1M_TXEN/M1P_RXDV_61") (pintype "passive"))
    )
    (net (code "110") (name "unconnected-(DD1-RG1_TXD0{slash}M1M_TXD0{slash}M1P_RXD0-Pad60)") (class "Default")
      (node (ref "DD1") (pin "60") (pinfunction "RG1_TXD0/M1M_TXD0/M1P_RXD0_60") (pintype "passive"))
    )
    (net (code "111") (name "unconnected-(DD1-RG1_TXD1{slash}M1M_TXD1{slash}M1P_RXD1-Pad59)") (class "Default")
      (node (ref "DD1") (pin "59") (pinfunction "RG1_TXD1/M1M_TXD1/M1P_RXD1_59") (pintype "passive"))
    )
    (net (code "112") (name "unconnected-(DD1-RG1_TXD2{slash}M1M_TXD2{slash}M1P_RXD2-Pad58)") (class "Default")
      (node (ref "DD1") (pin "58") (pinfunction "RG1_TXD2/M1M_TXD2/M1P_RXD2_58") (pintype "passive"))
    )
    (net (code "113") (name "unconnected-(DD1-RG1_TXD3{slash}M1M_TXD3{slash}M1P_RXD3-Pad57)") (class "Default")
      (node (ref "DD1") (pin "57") (pinfunction "RG1_TXD3/M1M_TXD3/M1P_RXD3_57") (pintype "passive"))
    )
    (net (code "114") (name "unconnected-(DD1-RG2_TXCTL{slash}M2M_TXEN{slash}M2P_RXDV-Pad45)") (class "Default")
      (node (ref "DD1") (pin "45") (pinfunction "RG2_TXCTL/M2M_TXEN/M2P_RXDV_45") (pintype "passive"))
    )
    (net (code "115") (name "unconnected-(DD1-RG2_TXD0{slash}M2M_TXD0{slash}M2P_RXD0-Pad44)") (class "Default")
      (node (ref "DD1") (pin "44") (pinfunction "RG2_TXD0/M2M_TXD0/M2P_RXD0_44") (pintype "passive"))
    )
    (net (code "116") (name "unconnected-(DD1-RG2_TXD1{slash}M2M_TXD1{slash}M2P_RXD1-Pad43)") (class "Default")
      (node (ref "DD1") (pin "43") (pinfunction "RG2_TXD1/M2M_TXD1/M2P_RXD1_43") (pintype "passive"))
    )
    (net (code "117") (name "unconnected-(DD1-RG2_TXD2{slash}M2M_TXD2{slash}M2P_RXD2-Pad42)") (class "Default")
      (node (ref "DD1") (pin "42") (pinfunction "RG2_TXD2/M2M_TXD2/M2P_RXD2_42") (pintype "passive"))
    )
    (net (code "118") (name "unconnected-(DD1-RG2_TXD3{slash}M2M_TXD3{slash}M2P_RXD3-Pad41)") (class "Default")
      (node (ref "DD1") (pin "41") (pinfunction "RG2_TXD3/M2M_TXD3/M2P_RXD3_41") (pintype "passive"))
    )
    (net (code "119") (name "unconnected-(DD1-RTT1-Pad15)") (class "Default")
      (node (ref "DD1") (pin "15") (pinfunction "RTT1_15") (pintype "passive"))
    )
    (net (code "120") (name "unconnected-(DD1-RTT2-Pad16)") (class "Default")
      (node (ref "DD1") (pin "16") (pinfunction "RTT2_16") (pintype "passive"))
    )
    (net (code "121") (name "unconnected-(DD1-SPIS_CK{slash}SCK-Pad93)") (class "Default")
      (node (ref "DD1") (pin "93") (pinfunction "SPIS_CK/SCK_93") (pintype "passive"))
    )
    (net (code "122") (name "unconnected-(DD1-SPIS_CS-Pad92)") (class "Default")
      (node (ref "DD1") (pin "92") (pinfunction "SPIS_CS_92") (pintype "passive"))
    )
    (net (code "123") (name "unconnected-(DD1-SPIS_DI{slash}SDA-Pad94)") (class "Default")
      (node (ref "DD1") (pin "94") (pinfunction "SPIS_DI/SDA_94") (pintype "passive"))
    )
    (net (code "124") (name "unconnected-(DD1-SPIS_DO-Pad95)") (class "Default")
      (node (ref "DD1") (pin "95") (pinfunction "SPIS_DO_95") (pintype "passive"))
    )
  )
)
